# shelves_v05.net
KiCad netlist of a schematic drawn in EAGLE
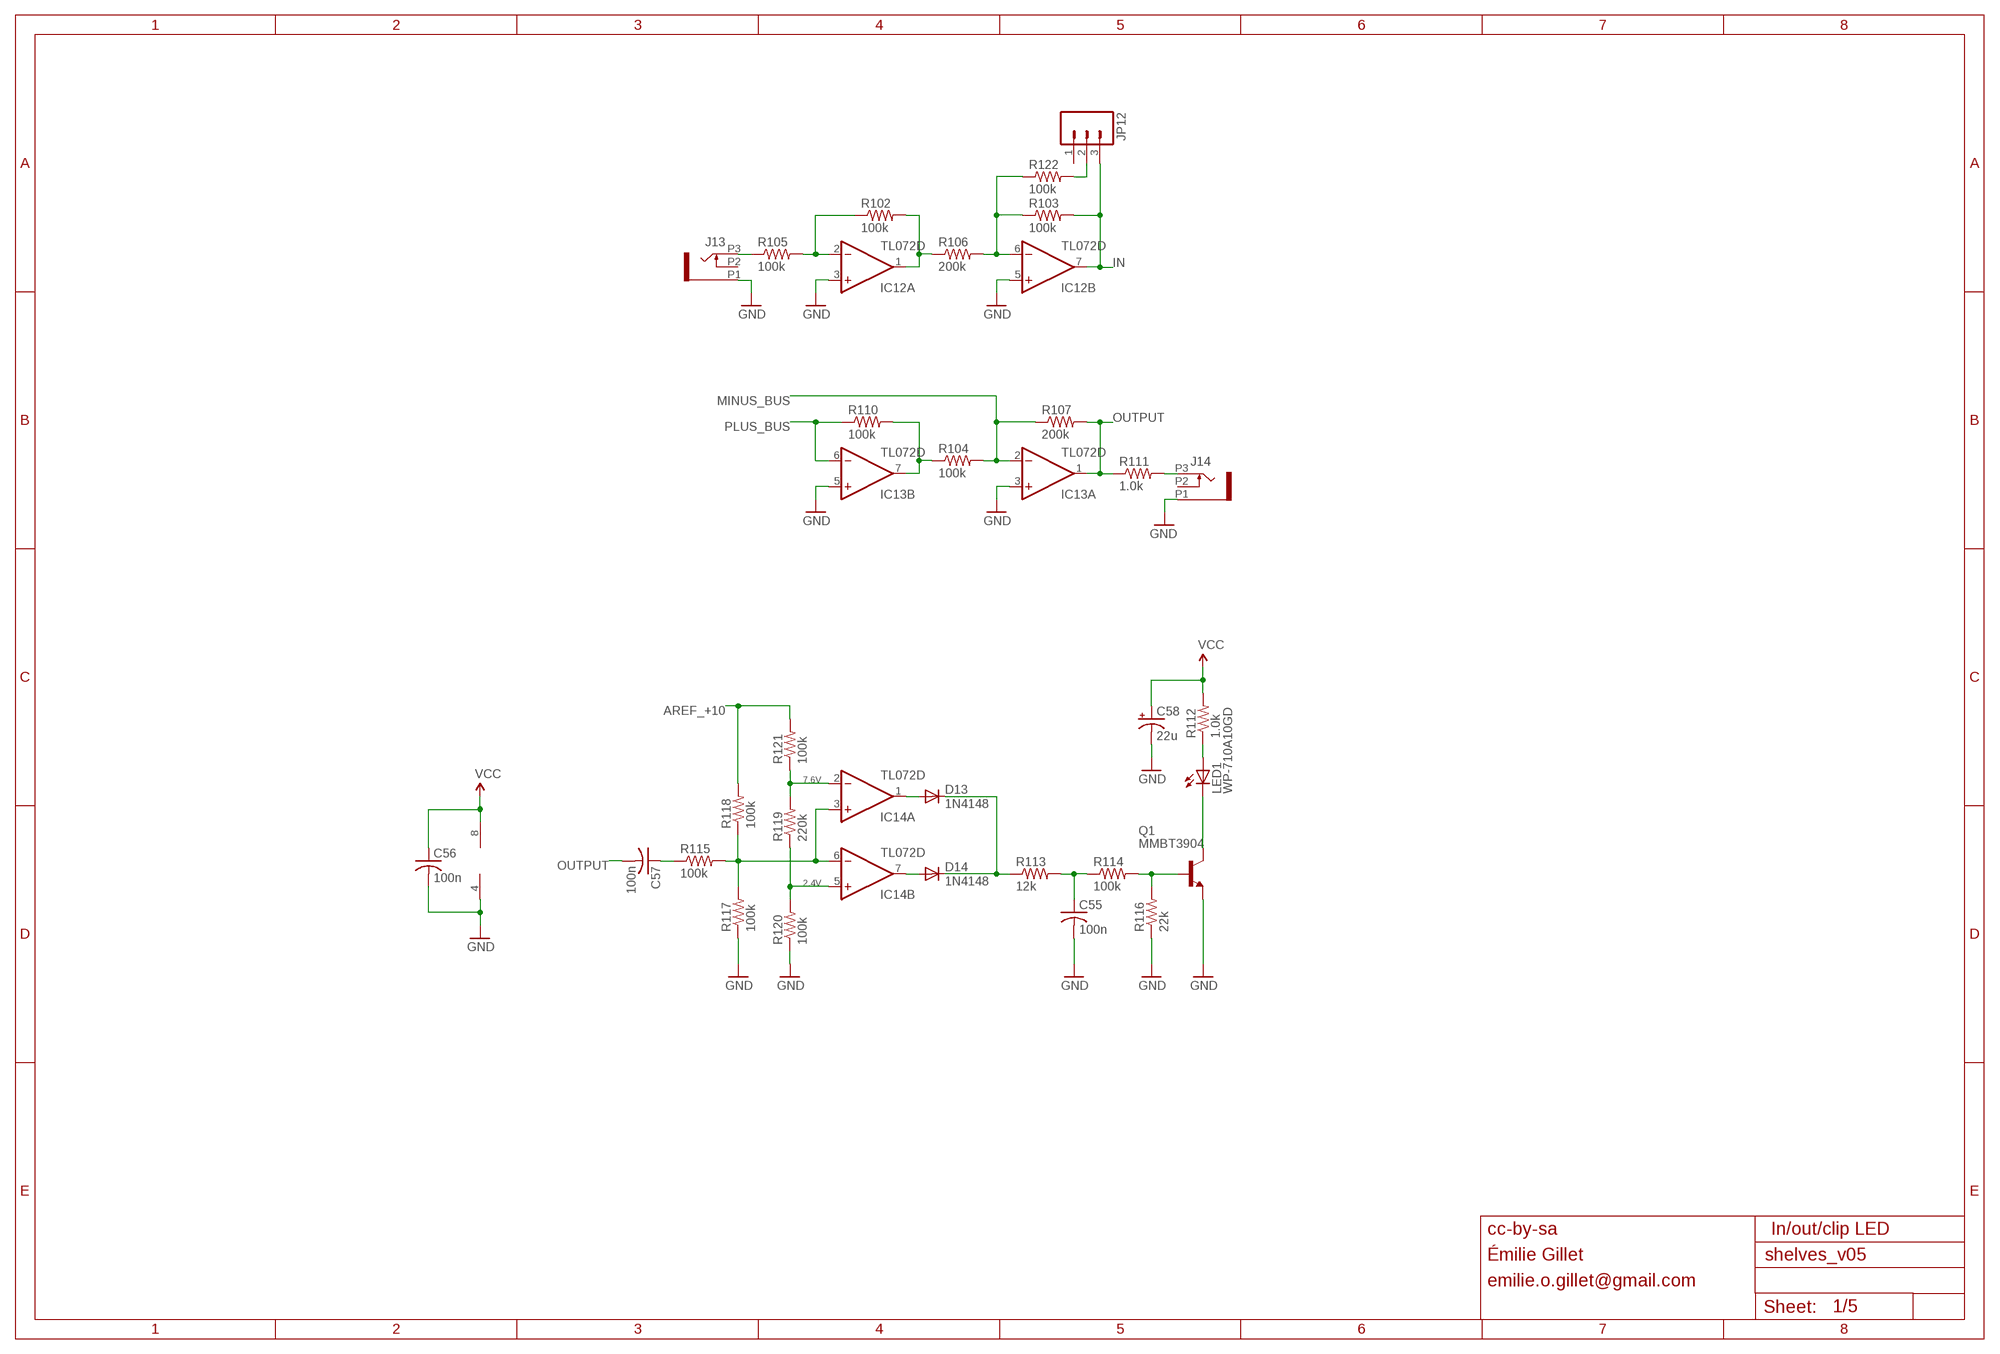
[diagram p0: schematic, sheet 1]
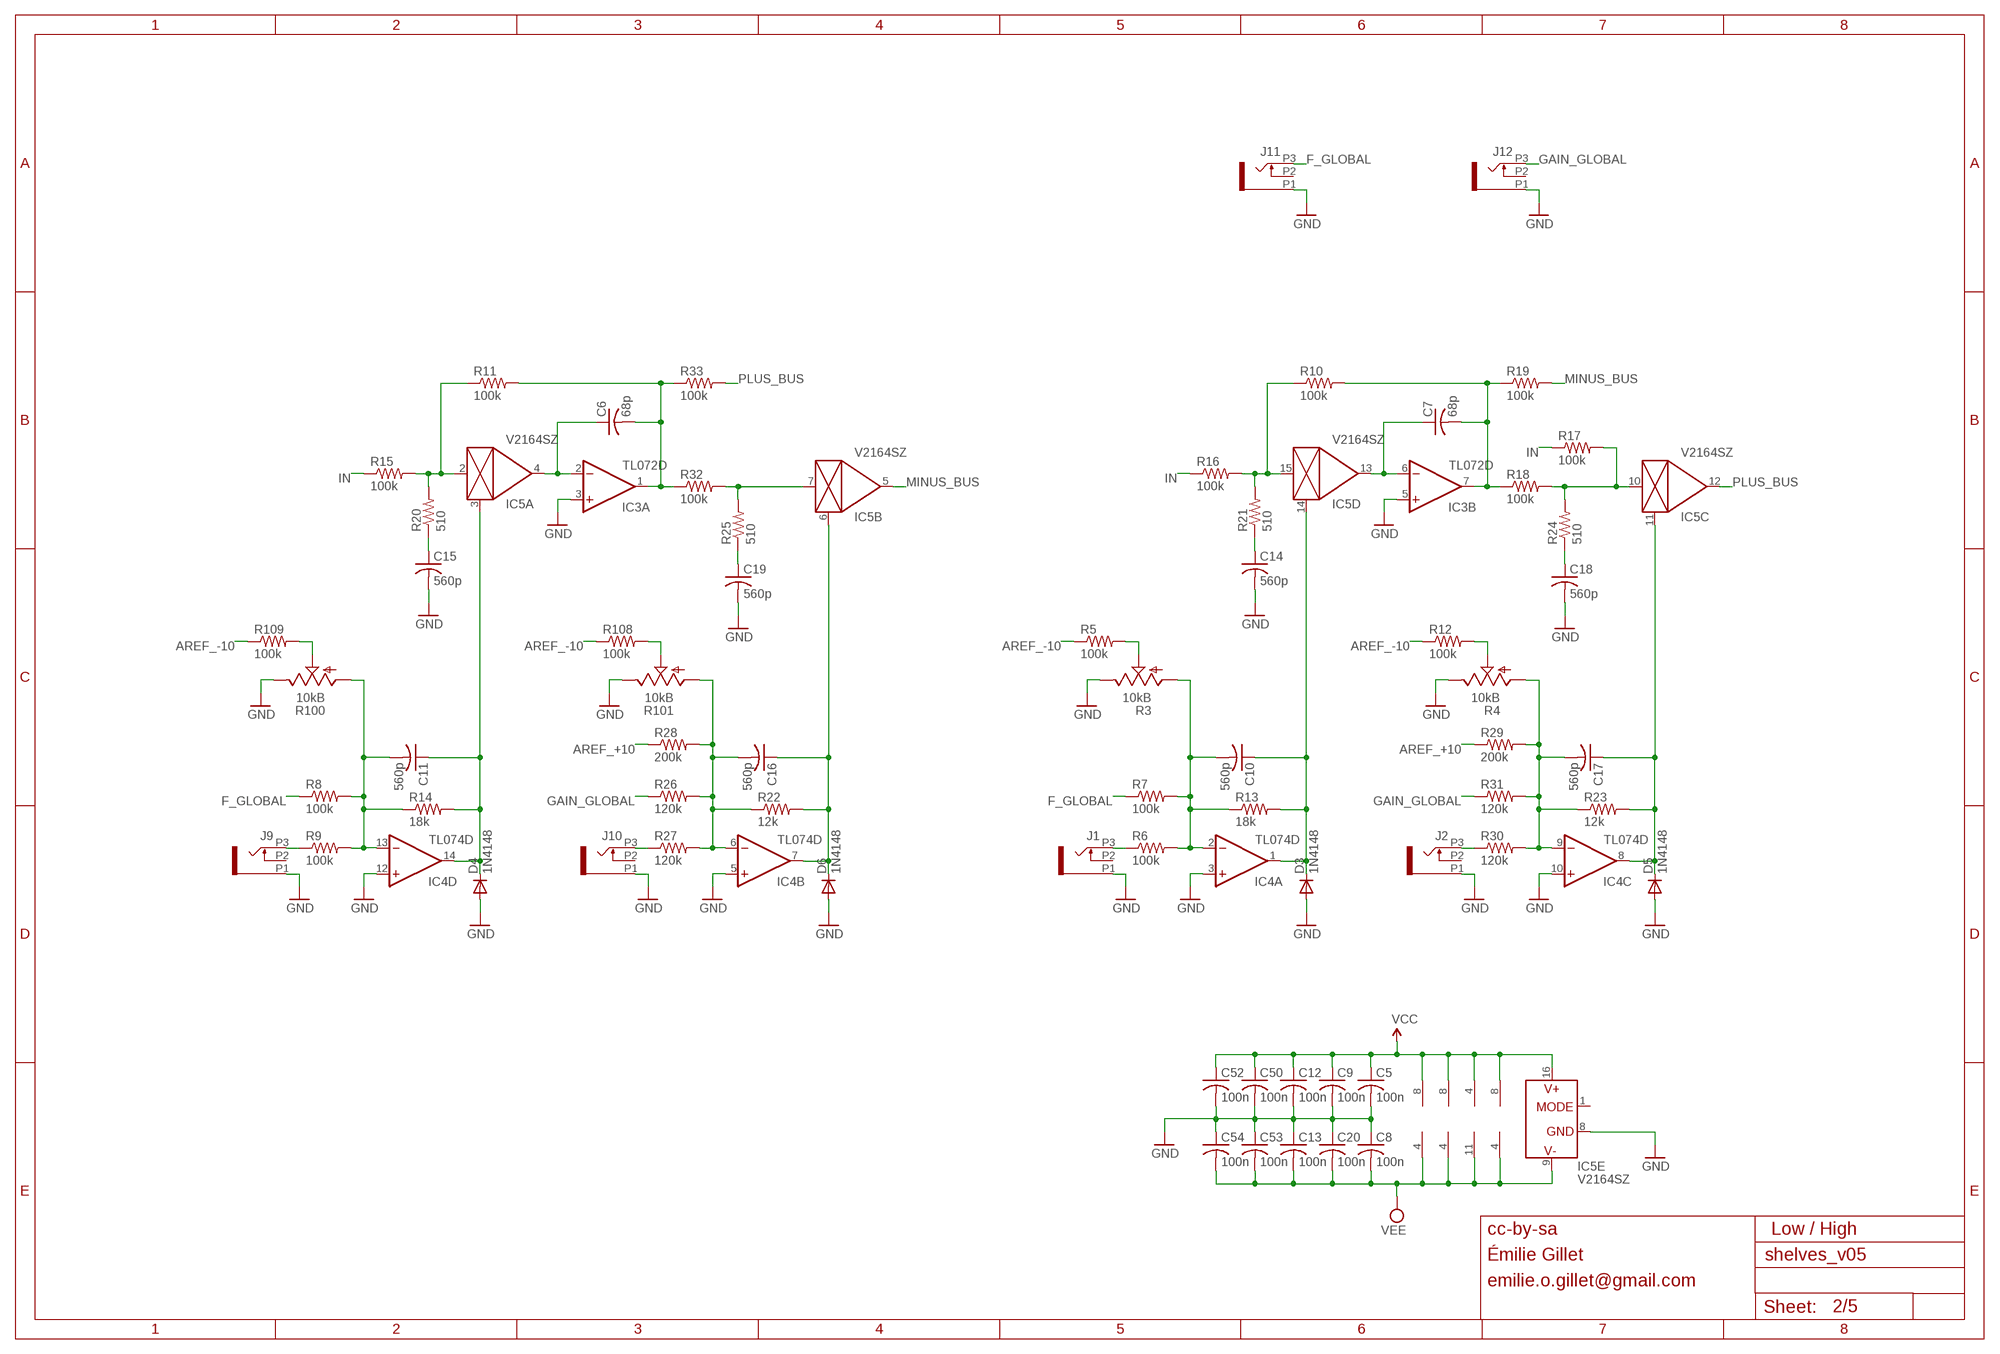
[diagram p1: schematic, sheet 2]
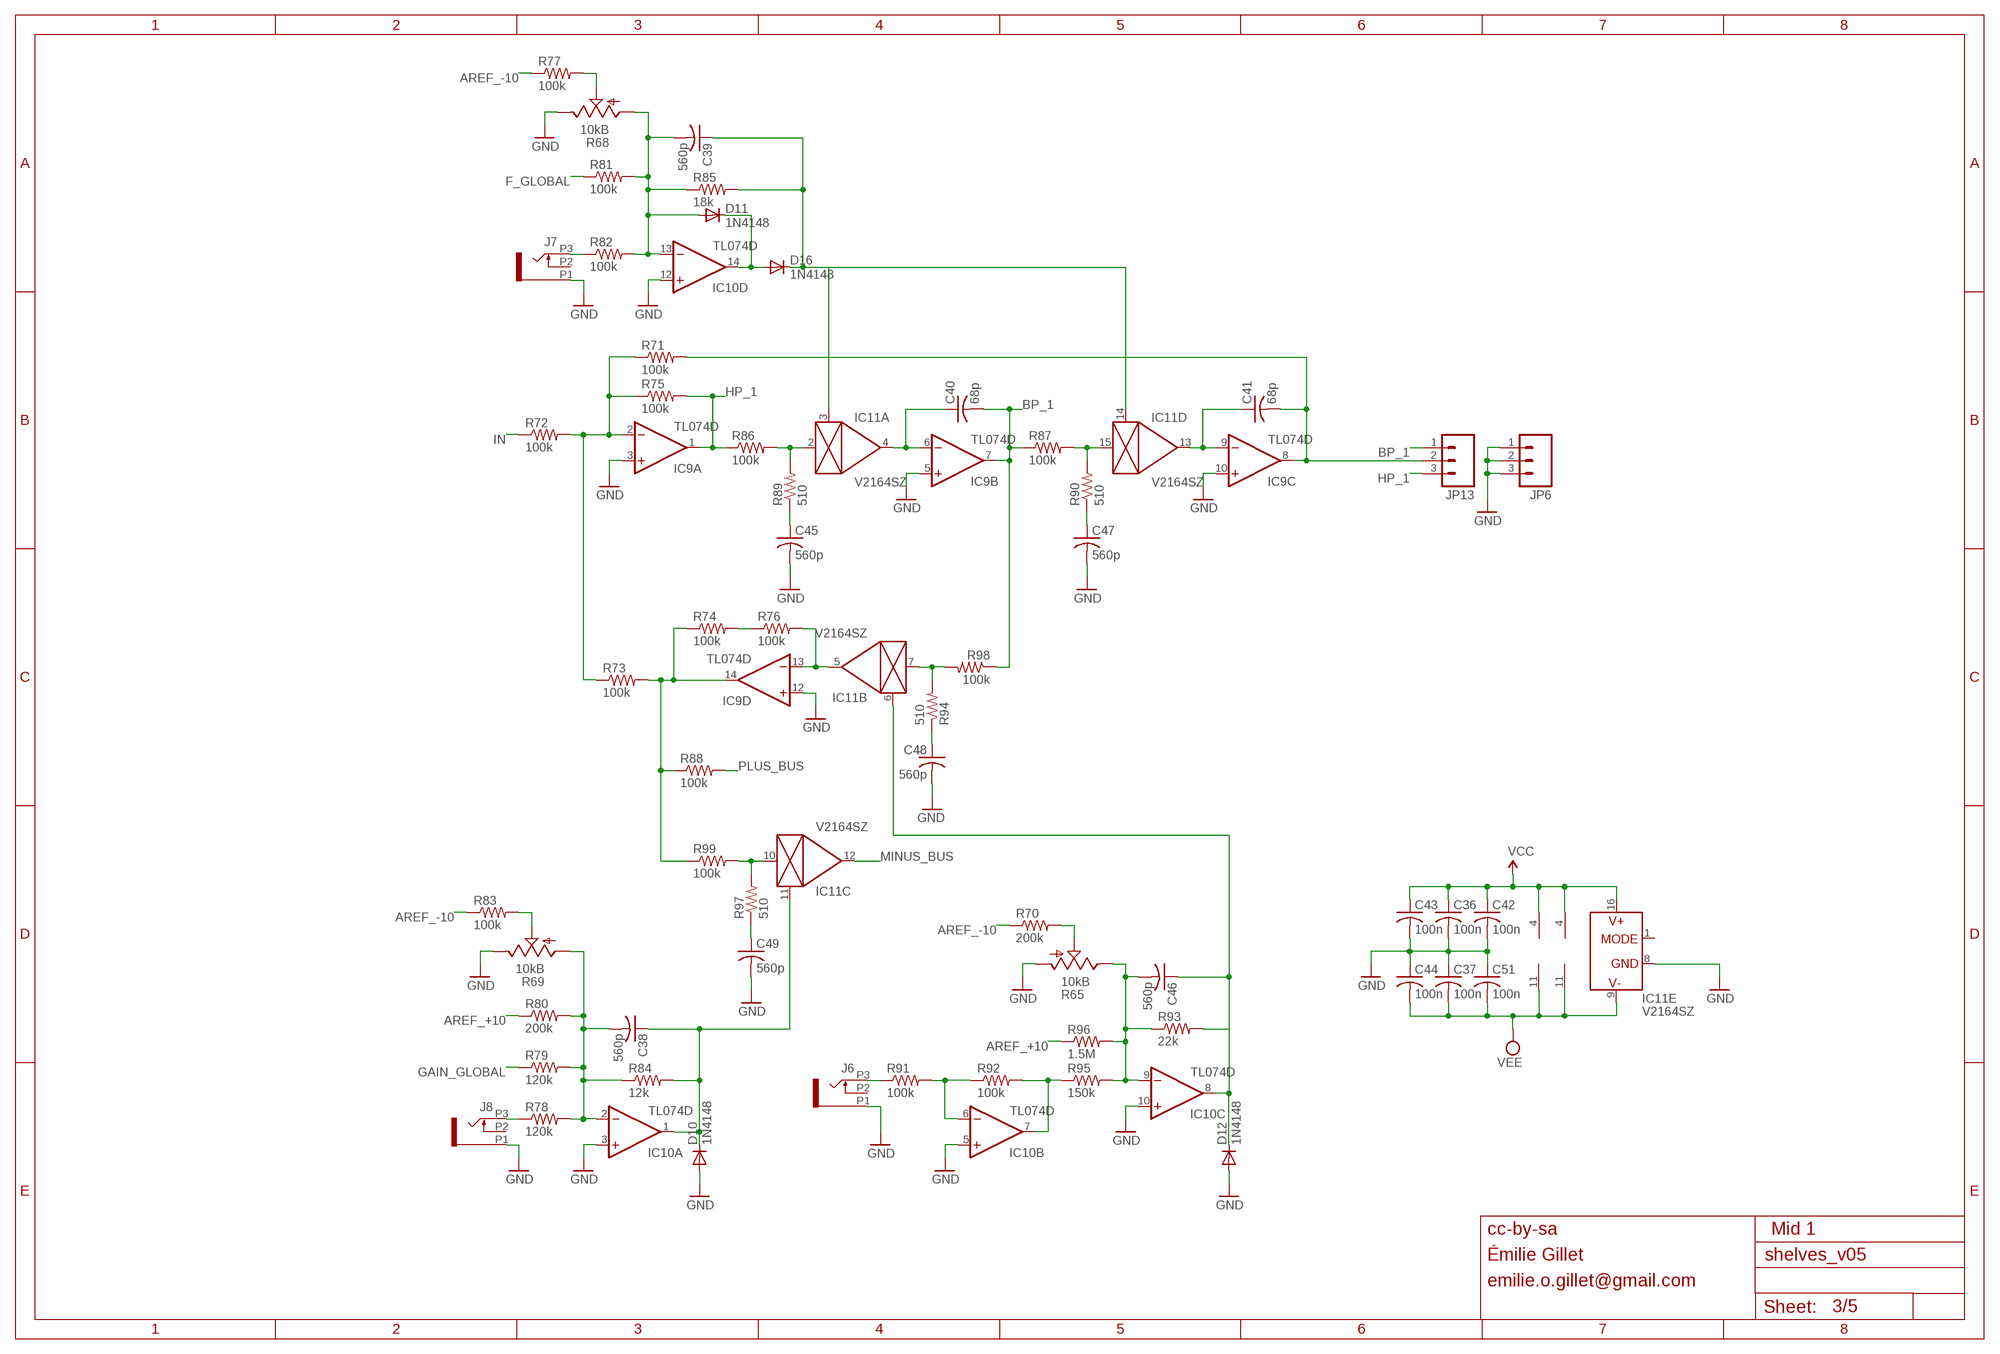
[diagram p2: schematic, sheet 3]
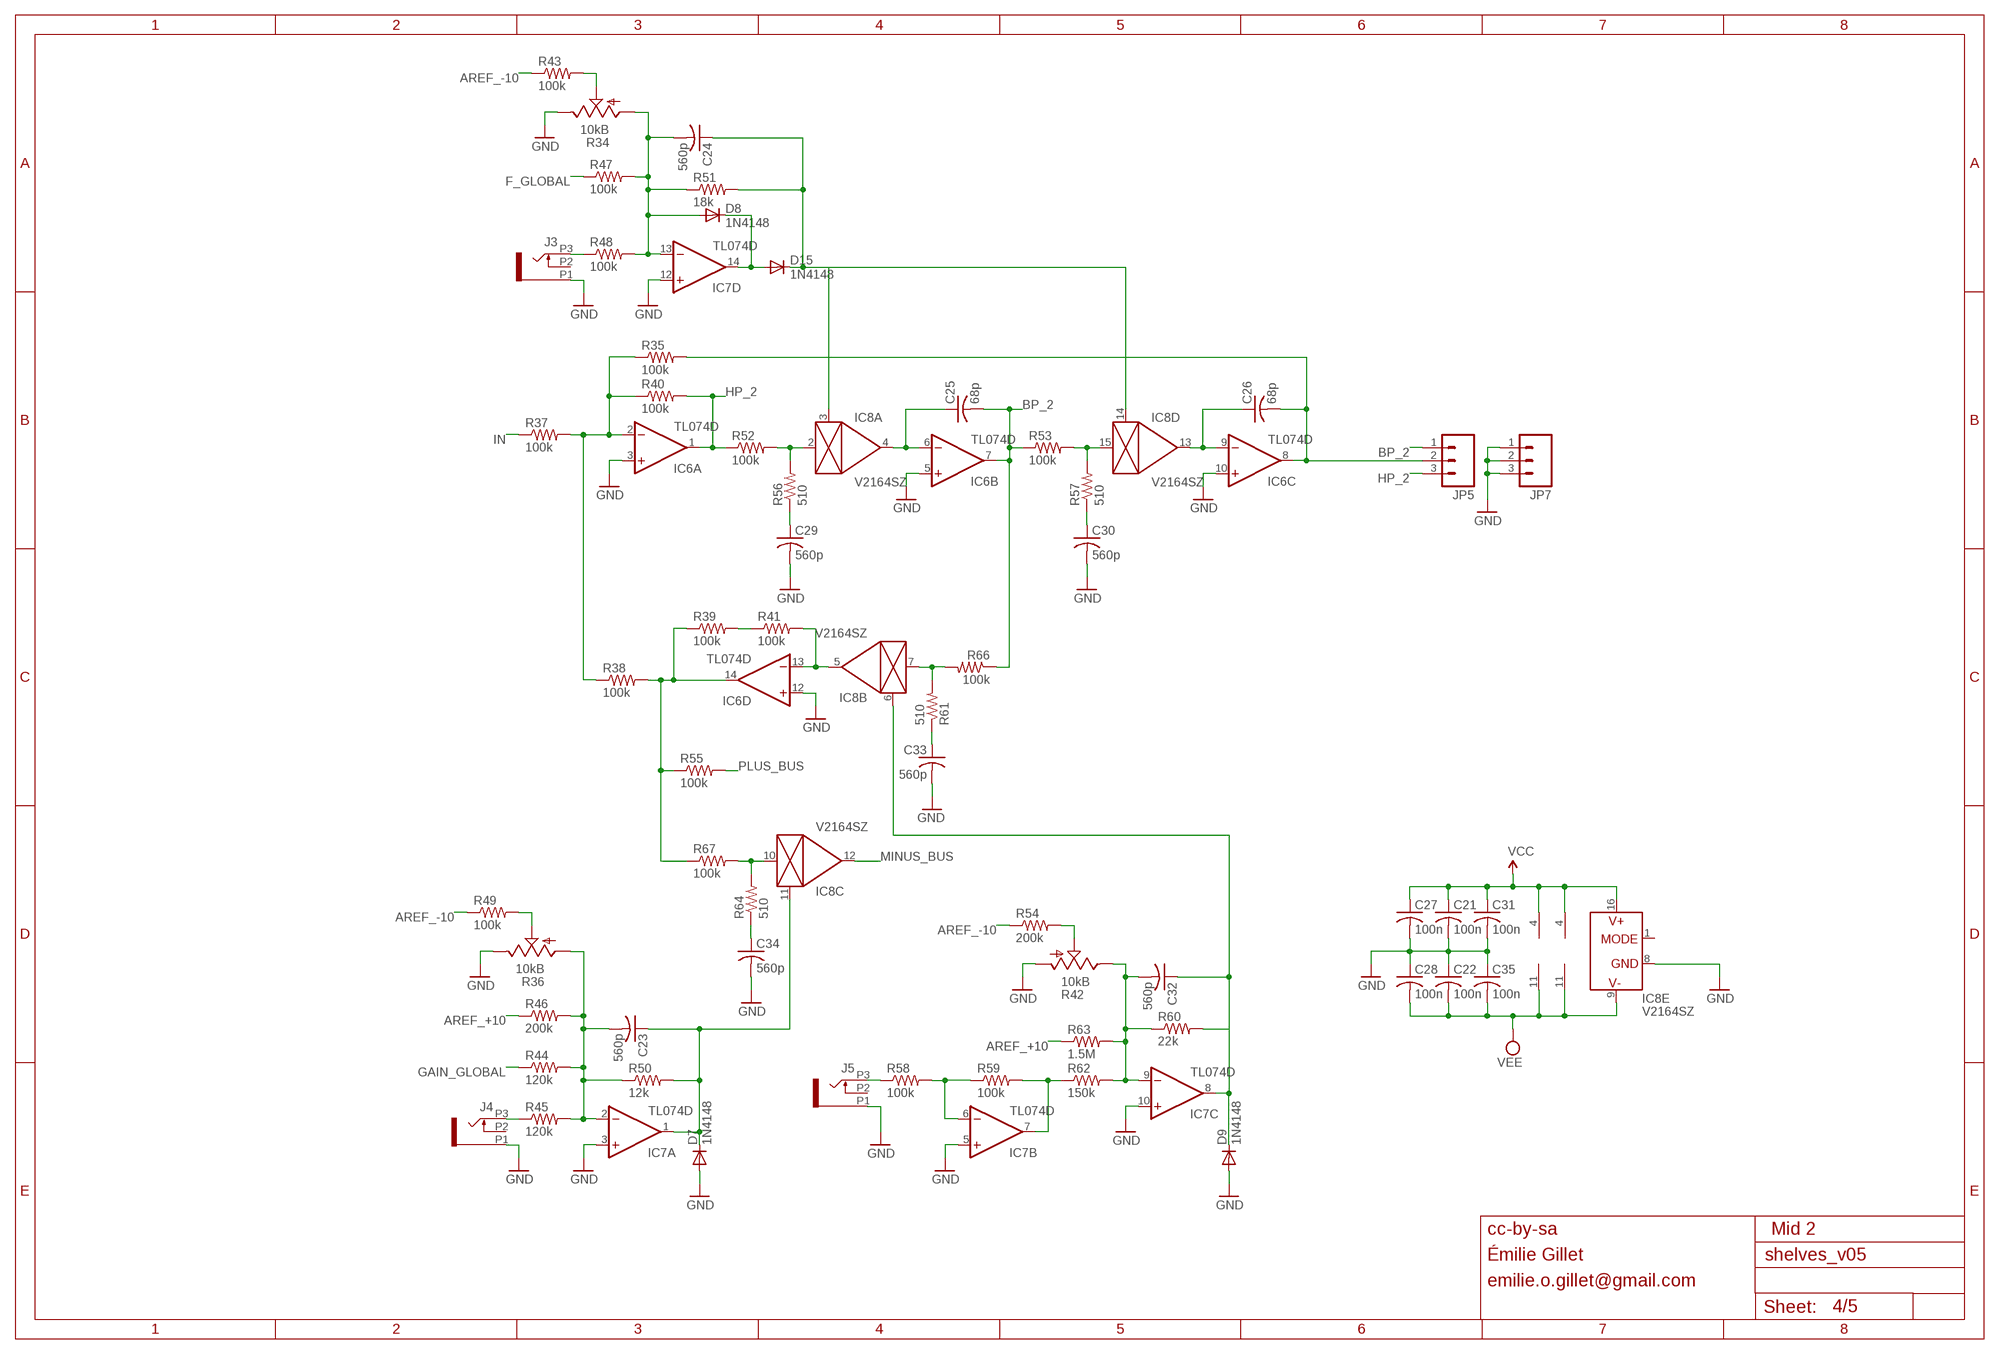
[diagram p3: schematic, sheet 4]
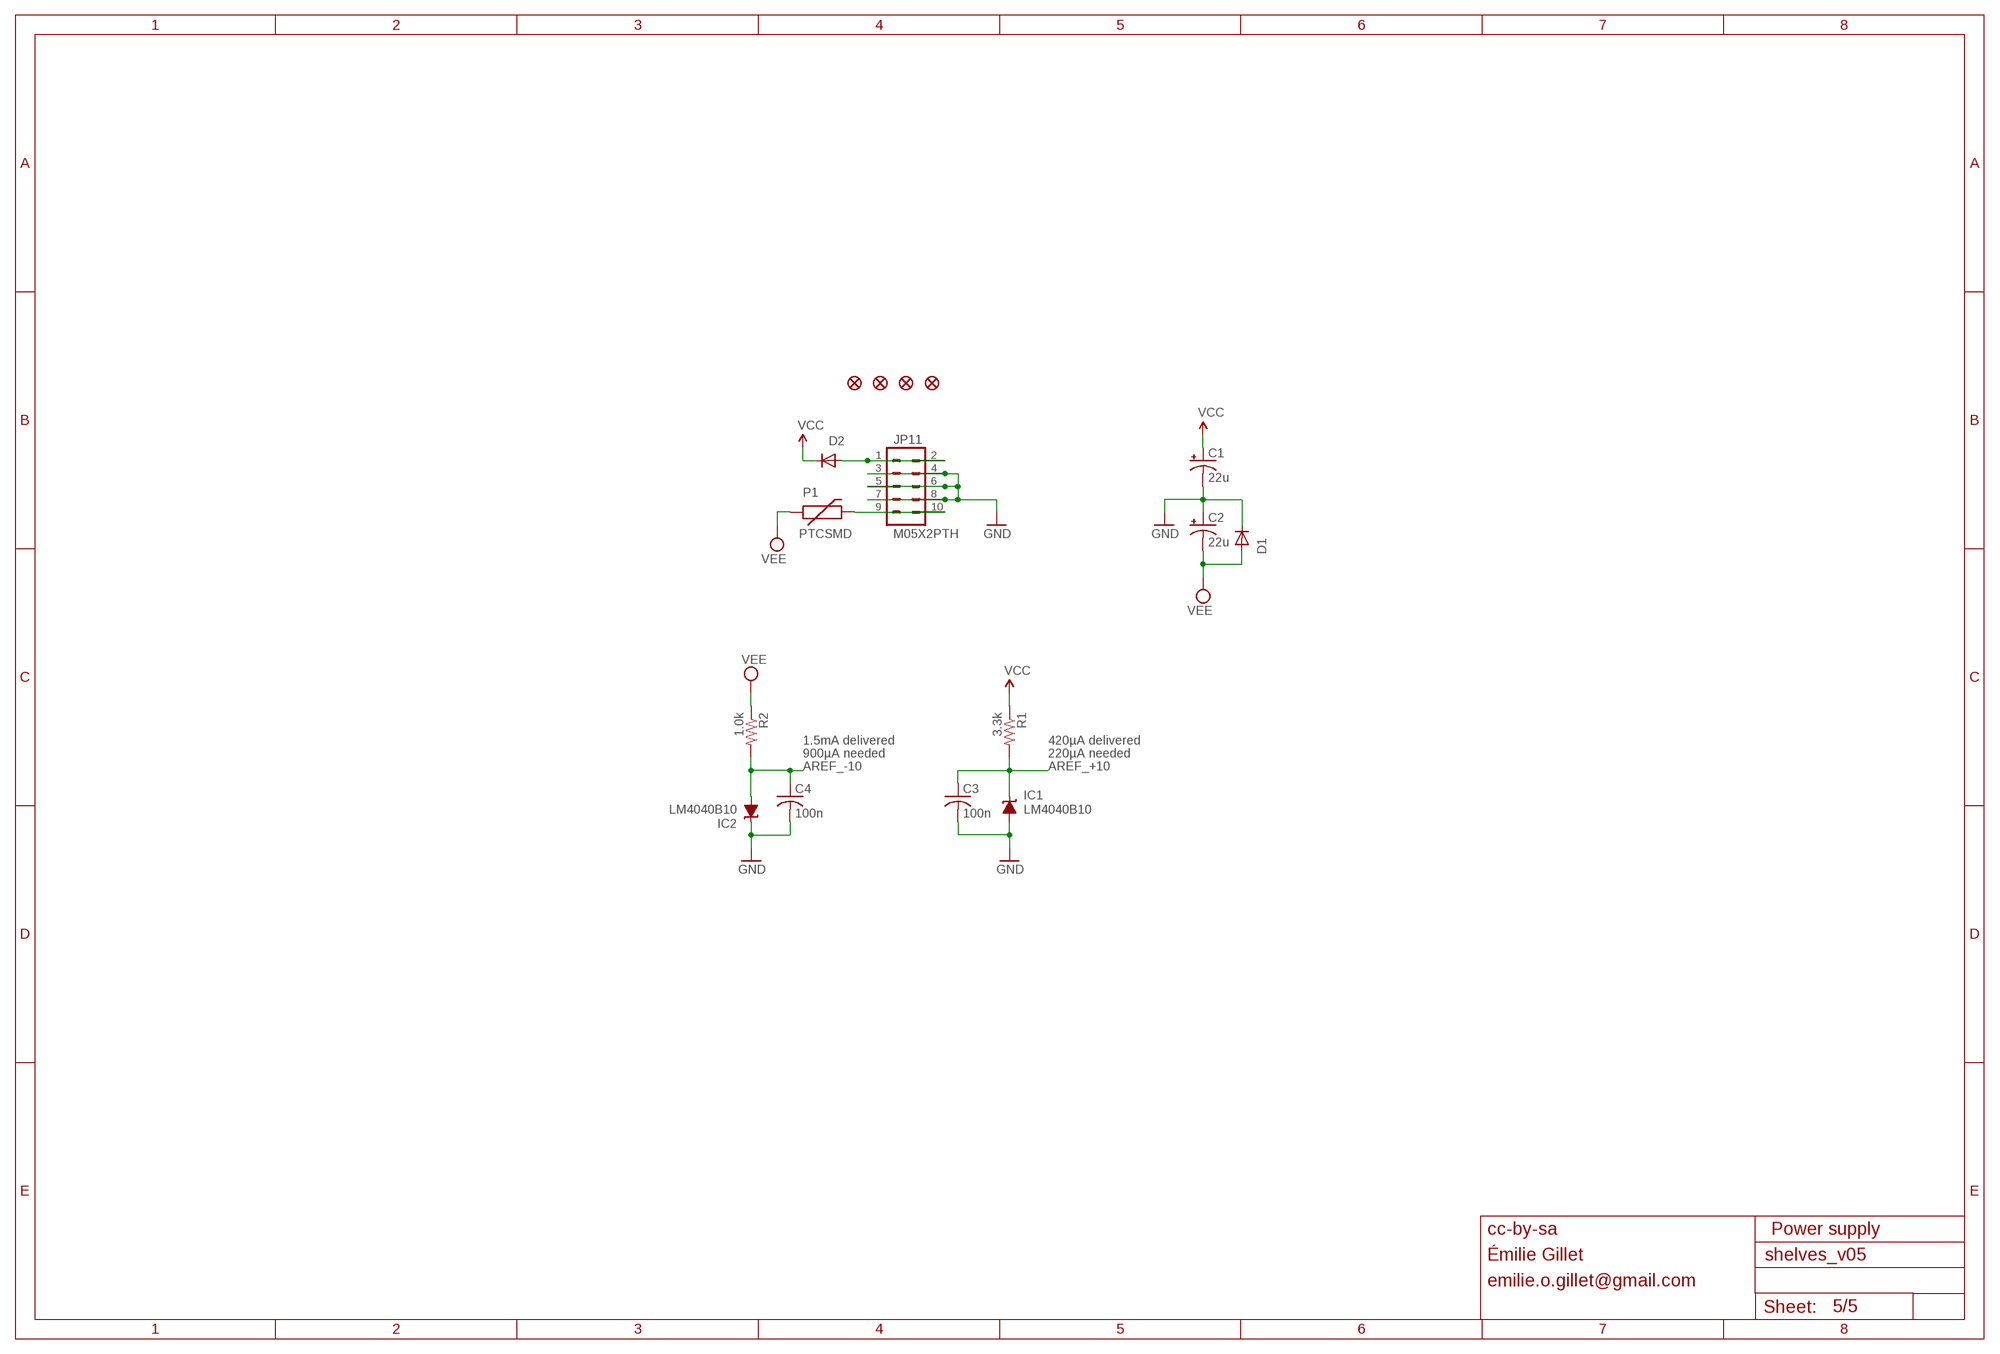
[diagram p4: schematic, sheet 5]

(export (version "E")
  (design (tool "Eeschema 10.0.6"))
  (components
    (comp (ref "C21")
      (value "100n")
      (footprint "eagle-import:C0603")
      (libsource (lib "eagle-import") (part "C-USC0603"))
    )
    (comp (ref "C22")
      (value "100n")
      (footprint "eagle-import:C0603")
      (libsource (lib "eagle-import") (part "C-USC0603"))
    )
    (comp (ref "C23")
      (value "560p")
      (footprint "eagle-import:C0603")
      (libsource (lib "eagle-import") (part "C-USC0603"))
    )
    (comp (ref "C24")
      (value "560p")
      (footprint "eagle-import:C0603")
      (libsource (lib "eagle-import") (part "C-USC0603"))
    )
    (comp (ref "C25")
      (value "68p")
      (footprint "eagle-import:C0603")
      (libsource (lib "eagle-import") (part "C-USC0603"))
    )
    (comp (ref "C26")
      (value "68p")
      (footprint "eagle-import:C0603")
      (libsource (lib "eagle-import") (part "C-USC0603"))
    )
    (comp (ref "C27")
      (value "100n")
      (footprint "eagle-import:C0603")
      (libsource (lib "eagle-import") (part "C-USC0603"))
    )
    (comp (ref "C28")
      (value "100n")
      (footprint "eagle-import:C0603")
      (libsource (lib "eagle-import") (part "C-USC0603"))
    )
    (comp (ref "C29")
      (value "560p")
      (footprint "eagle-import:C0603")
      (libsource (lib "eagle-import") (part "C-USC0603"))
    )
    (comp (ref "C30")
      (value "560p")
      (footprint "eagle-import:C0603")
      (libsource (lib "eagle-import") (part "C-USC0603"))
    )
    (comp (ref "C31")
      (value "100n")
      (footprint "eagle-import:C0603")
      (libsource (lib "eagle-import") (part "C-USC0603"))
    )
    (comp (ref "C32")
      (value "560p")
      (footprint "eagle-import:C0603")
      (libsource (lib "eagle-import") (part "C-USC0603"))
    )
    (comp (ref "C33")
      (value "560p")
      (footprint "eagle-import:C0603")
      (libsource (lib "eagle-import") (part "C-USC0603"))
    )
    (comp (ref "C34")
      (value "560p")
      (footprint "eagle-import:C0603")
      (libsource (lib "eagle-import") (part "C-USC0603"))
    )
    (comp (ref "C35")
      (value "100n")
      (footprint "eagle-import:C0603")
      (libsource (lib "eagle-import") (part "C-USC0603"))
    )
    (comp (ref "D7")
      (value "1N4148")
      (footprint "eagle-import:SOD323-W")
      (libsource (lib "eagle-import") (part "DIODE-SOD323-W"))
    )
    (comp (ref "D8")
      (value "1N4148")
      (footprint "eagle-import:SOD323-W")
      (libsource (lib "eagle-import") (part "DIODE-SOD323-W"))
    )
    (comp (ref "D9")
      (value "1N4148")
      (footprint "eagle-import:SOD323-W")
      (libsource (lib "eagle-import") (part "DIODE-SOD323-W"))
    )
    (comp (ref "D15")
      (value "1N4148")
      (footprint "eagle-import:SOD323-W")
      (libsource (lib "eagle-import") (part "DIODE-SOD323-W"))
    )
    (comp (ref "IC6")
      (value "TL074D")
      (footprint "eagle-import:SO14")
      (libsource (lib "eagle-import") (part "TL074D"))
    )
    (comp (ref "IC7")
      (value "TL074D")
      (footprint "eagle-import:SO14")
      (libsource (lib "eagle-import") (part "TL074D"))
    )
    (comp (ref "IC8")
      (value "V2164SZ")
      (footprint "eagle-import:SOIC16N")
      (libsource (lib "eagle-import") (part "SSM2164S"))
    )
    (comp (ref "J3")
      (value "PJ301_THONKICONN6")
      (footprint "eagle-import:WQP_PJ_301M6")
      (libsource (lib "eagle-import") (part "PJ301_THONKICONN6"))
    )
    (comp (ref "J4")
      (value "PJ301_THONKICONN6")
      (footprint "eagle-import:WQP_PJ_301M6")
      (libsource (lib "eagle-import") (part "PJ301_THONKICONN6"))
    )
    (comp (ref "J5")
      (value "PJ301_THONKICONN6")
      (footprint "eagle-import:WQP_PJ_301M6")
      (libsource (lib "eagle-import") (part "PJ301_THONKICONN6"))
    )
    (comp (ref "JP5")
      (value "M03PTH")
      (footprint "eagle-import:1X03")
      (libsource (lib "eagle-import") (part "M03PTH"))
    )
    (comp (ref "JP7")
      (value "M03PTH")
      (footprint "eagle-import:1X03")
      (libsource (lib "eagle-import") (part "M03PTH"))
    )
    (comp (ref "R34")
      (value "10kB")
      (footprint "eagle-import:ALPS_POT_VERTICAL_PS")
      (libsource (lib "eagle-import") (part "POT_USVERTICAL_PS"))
    )
    (comp (ref "R35")
      (value "100k")
      (footprint "eagle-import:R0603")
      (libsource (lib "eagle-import") (part "R-US_R0603"))
    )
    (comp (ref "R36")
      (value "10kB")
      (footprint "eagle-import:ALPS_POT_VERTICAL_PS")
      (libsource (lib "eagle-import") (part "POT_USVERTICAL_PS"))
    )
    (comp (ref "R37")
      (value "100k")
      (footprint "eagle-import:R0603")
      (libsource (lib "eagle-import") (part "R-US_R0603"))
    )
    (comp (ref "R38")
      (value "100k")
      (footprint "eagle-import:R0603")
      (libsource (lib "eagle-import") (part "R-US_R0603"))
    )
    (comp (ref "R39")
      (value "100k")
      (footprint "eagle-import:R0603")
      (libsource (lib "eagle-import") (part "R-US_R0603"))
    )
    (comp (ref "R40")
      (value "100k")
      (footprint "eagle-import:R0603")
      (libsource (lib "eagle-import") (part "R-US_R0603"))
    )
    (comp (ref "R41")
      (value "100k")
      (footprint "eagle-import:R0603")
      (libsource (lib "eagle-import") (part "R-US_R0603"))
    )
    (comp (ref "R42")
      (value "10kB")
      (footprint "eagle-import:ALPS_POT_VERTICAL")
      (libsource (lib "eagle-import") (part "POT_USVERTICAL"))
    )
    (comp (ref "R43")
      (value "100k")
      (footprint "eagle-import:R0603")
      (libsource (lib "eagle-import") (part "R-US_R0603"))
    )
    (comp (ref "R44")
      (value "120k")
      (footprint "eagle-import:R0603")
      (libsource (lib "eagle-import") (part "R-US_R0603"))
    )
    (comp (ref "R45")
      (value "120k")
      (footprint "eagle-import:R0603")
      (libsource (lib "eagle-import") (part "R-US_R0603"))
    )
    (comp (ref "R46")
      (value "200k")
      (footprint "eagle-import:R0603")
      (libsource (lib "eagle-import") (part "R-US_R0603"))
    )
    (comp (ref "R47")
      (value "100k")
      (footprint "eagle-import:R0603")
      (libsource (lib "eagle-import") (part "R-US_R0603"))
    )
    (comp (ref "R48")
      (value "100k")
      (footprint "eagle-import:R0603")
      (libsource (lib "eagle-import") (part "R-US_R0603"))
    )
    (comp (ref "R49")
      (value "100k")
      (footprint "eagle-import:R0603")
      (libsource (lib "eagle-import") (part "R-US_R0603"))
    )
    (comp (ref "R50")
      (value "12k")
      (footprint "eagle-import:R0603")
      (libsource (lib "eagle-import") (part "R-US_R0603"))
    )
    (comp (ref "R51")
      (value "18k")
      (footprint "eagle-import:R0603")
      (libsource (lib "eagle-import") (part "R-US_R0603"))
    )
    (comp (ref "R52")
      (value "100k")
      (footprint "eagle-import:R0603")
      (libsource (lib "eagle-import") (part "R-US_R0603"))
    )
    (comp (ref "R53")
      (value "100k")
      (footprint "eagle-import:R0603")
      (libsource (lib "eagle-import") (part "R-US_R0603"))
    )
    (comp (ref "R54")
      (value "200k")
      (footprint "eagle-import:R0603")
      (libsource (lib "eagle-import") (part "R-US_R0603"))
    )
    (comp (ref "R55")
      (value "100k")
      (footprint "eagle-import:R0603")
      (libsource (lib "eagle-import") (part "R-US_R0603"))
    )
    (comp (ref "R56")
      (value "510")
      (footprint "eagle-import:R0603")
      (libsource (lib "eagle-import") (part "R-US_R0603"))
    )
    (comp (ref "R57")
      (value "510")
      (footprint "eagle-import:R0603")
      (libsource (lib "eagle-import") (part "R-US_R0603"))
    )
    (comp (ref "R58")
      (value "100k")
      (footprint "eagle-import:R0603")
      (libsource (lib "eagle-import") (part "R-US_R0603"))
    )
    (comp (ref "R59")
      (value "100k")
      (footprint "eagle-import:R0603")
      (libsource (lib "eagle-import") (part "R-US_R0603"))
    )
    (comp (ref "R60")
      (value "22k")
      (footprint "eagle-import:R0603")
      (libsource (lib "eagle-import") (part "R-US_R0603"))
    )
    (comp (ref "R61")
      (value "510")
      (footprint "eagle-import:R0603")
      (libsource (lib "eagle-import") (part "R-US_R0603"))
    )
    (comp (ref "R62")
      (value "150k")
      (footprint "eagle-import:R0603")
      (libsource (lib "eagle-import") (part "R-US_R0603"))
    )
    (comp (ref "R63")
      (value "1.5M")
      (footprint "eagle-import:R0603")
      (libsource (lib "eagle-import") (part "R-US_R0603"))
    )
    (comp (ref "R64")
      (value "510")
      (footprint "eagle-import:R0603")
      (libsource (lib "eagle-import") (part "R-US_R0603"))
    )
    (comp (ref "R66")
      (value "100k")
      (footprint "eagle-import:R0603")
      (libsource (lib "eagle-import") (part "R-US_R0603"))
    )
    (comp (ref "R67")
      (value "100k")
      (footprint "eagle-import:R0603")
      (libsource (lib "eagle-import") (part "R-US_R0603"))
    )
    (comp (ref "C55")
      (value "100n")
      (footprint "eagle-import:C0603")
      (libsource (lib "eagle-import") (part "C-USC0603"))
    )
    (comp (ref "C56")
      (value "100n")
      (footprint "eagle-import:C0603")
      (libsource (lib "eagle-import") (part "C-USC0603"))
    )
    (comp (ref "C57")
      (value "100n")
      (footprint "eagle-import:C0603")
      (libsource (lib "eagle-import") (part "C-USC0603"))
    )
    (comp (ref "C58")
      (value "22u")
      (footprint "eagle-import:PANASONIC_C")
      (libsource (lib "eagle-import") (part "CPOL-USC"))
    )
    (comp (ref "D13")
      (value "1N4148")
      (footprint "eagle-import:SOD323-W")
      (libsource (lib "eagle-import") (part "DIODE-SOD323-W"))
    )
    (comp (ref "D14")
      (value "1N4148")
      (footprint "eagle-import:SOD323-W")
      (libsource (lib "eagle-import") (part "DIODE-SOD323-W"))
    )
    (comp (ref "IC12")
      (value "TL072D")
      (footprint "eagle-import:SO08")
      (libsource (lib "eagle-import") (part "TL072D"))
    )
    (comp (ref "IC13")
      (value "TL072D")
      (footprint "eagle-import:SO08")
      (libsource (lib "eagle-import") (part "TL072D"))
    )
    (comp (ref "IC14")
      (value "TL072D")
      (footprint "eagle-import:SO08")
      (libsource (lib "eagle-import") (part "TL072D"))
    )
    (comp (ref "J13")
      (value "PJ301_THONKICONN6")
      (footprint "eagle-import:WQP_PJ_301M6")
      (libsource (lib "eagle-import") (part "PJ301_THONKICONN6"))
    )
    (comp (ref "J14")
      (value "PJ301_THONKICONN6")
      (footprint "eagle-import:WQP_PJ_301M6")
      (libsource (lib "eagle-import") (part "PJ301_THONKICONN6"))
    )
    (comp (ref "JP12")
      (value "M03PTH")
      (footprint "eagle-import:1X03")
      (libsource (lib "eagle-import") (part "M03PTH"))
    )
    (comp (ref "LED1")
      (value "WP-710A10GD")
      (footprint "eagle-import:LED3MM")
      (libsource (lib "eagle-import") (part "LED3MM"))
    )
    (comp (ref "Q1")
      (value "MMBT3904")
      (footprint "eagle-import:SOT23-BEC")
      (libsource (lib "eagle-import") (part "-NPN-SOT23-BECMMBT3904LT1"))
    )
    (comp (ref "R102")
      (value "100k")
      (footprint "eagle-import:R0603")
      (libsource (lib "eagle-import") (part "R-US_R0603"))
    )
    (comp (ref "R103")
      (value "100k")
      (footprint "eagle-import:R0603")
      (libsource (lib "eagle-import") (part "R-US_R0603"))
    )
    (comp (ref "R104")
      (value "100k")
      (footprint "eagle-import:R0603")
      (libsource (lib "eagle-import") (part "R-US_R0603"))
    )
    (comp (ref "R105")
      (value "100k")
      (footprint "eagle-import:R0603")
      (libsource (lib "eagle-import") (part "R-US_R0603"))
    )
    (comp (ref "R106")
      (value "200k")
      (footprint "eagle-import:R0603")
      (libsource (lib "eagle-import") (part "R-US_R0603"))
    )
    (comp (ref "R107")
      (value "200k")
      (footprint "eagle-import:R0603")
      (libsource (lib "eagle-import") (part "R-US_R0603"))
    )
    (comp (ref "R110")
      (value "100k")
      (footprint "eagle-import:R0603")
      (libsource (lib "eagle-import") (part "R-US_R0603"))
    )
    (comp (ref "R111")
      (value "1.0k")
      (footprint "eagle-import:R0603")
      (libsource (lib "eagle-import") (part "R-US_R0603"))
    )
    (comp (ref "R112")
      (value "1.0k")
      (footprint "eagle-import:R0603")
      (libsource (lib "eagle-import") (part "R-US_R0603"))
    )
    (comp (ref "R113")
      (value "12k")
      (footprint "eagle-import:R0603")
      (libsource (lib "eagle-import") (part "R-US_R0603"))
    )
    (comp (ref "R114")
      (value "100k")
      (footprint "eagle-import:R0603")
      (libsource (lib "eagle-import") (part "R-US_R0603"))
    )
    (comp (ref "R115")
      (value "100k")
      (footprint "eagle-import:R0603")
      (libsource (lib "eagle-import") (part "R-US_R0603"))
    )
    (comp (ref "R116")
      (value "22k")
      (footprint "eagle-import:R0603")
      (libsource (lib "eagle-import") (part "R-US_R0603"))
    )
    (comp (ref "R117")
      (value "100k")
      (footprint "eagle-import:R0603")
      (libsource (lib "eagle-import") (part "R-US_R0603"))
    )
    (comp (ref "R118")
      (value "100k")
      (footprint "eagle-import:R0603")
      (libsource (lib "eagle-import") (part "R-US_R0603"))
    )
    (comp (ref "R119")
      (value "220k")
      (footprint "eagle-import:R0603")
      (libsource (lib "eagle-import") (part "R-US_R0603"))
    )
    (comp (ref "R120")
      (value "100k")
      (footprint "eagle-import:R0603")
      (libsource (lib "eagle-import") (part "R-US_R0603"))
    )
    (comp (ref "R121")
      (value "100k")
      (footprint "eagle-import:R0603")
      (libsource (lib "eagle-import") (part "R-US_R0603"))
    )
    (comp (ref "R122")
      (value "100k")
      (footprint "eagle-import:R0603")
      (libsource (lib "eagle-import") (part "R-US_R0603"))
    )
    (comp (ref "C1")
      (value "22u")
      (footprint "eagle-import:PANASONIC_C")
      (libsource (lib "eagle-import") (part "CPOL-USC"))
    )
    (comp (ref "C2")
      (value "22u")
      (footprint "eagle-import:PANASONIC_C")
      (libsource (lib "eagle-import") (part "CPOL-USC"))
    )
    (comp (ref "C3")
      (value "100n")
      (footprint "eagle-import:C0603")
      (libsource (lib "eagle-import") (part "C-USC0603"))
    )
    (comp (ref "C4")
      (value "100n")
      (footprint "eagle-import:C0603")
      (libsource (lib "eagle-import") (part "C-USC0603"))
    )
    (comp (ref "D1")
      (value "1N5819HW")
      (footprint "eagle-import:SOD123")
      (libsource (lib "eagle-import") (part "DIODE-SOD123"))
    )
    (comp (ref "D2")
      (value "1N5819HW")
      (footprint "eagle-import:SOD123")
      (libsource (lib "eagle-import") (part "DIODE-SOD123"))
    )
    (comp (ref "IC1")
      (value "LM4040B10")
      (footprint "eagle-import:DBZ_R-PDSO-G3")
      (libsource (lib "eagle-import") (part "LM4041DBZB12"))
    )
    (comp (ref "IC2")
      (value "LM4040B10")
      (footprint "eagle-import:DBZ_R-PDSO-G3")
      (libsource (lib "eagle-import") (part "LM4041DBZB12"))
    )
    (comp (ref "JP1")
      (value "FIDUCIAL1X2")
      (footprint "eagle-import:FIDUCIAL-1X2")
      (libsource (lib "eagle-import") (part "FIDUCIAL1X2"))
    )
    (comp (ref "JP2")
      (value "FIDUCIAL1X2")
      (footprint "eagle-import:FIDUCIAL-1X2")
      (libsource (lib "eagle-import") (part "FIDUCIAL1X2"))
    )
    (comp (ref "JP3")
      (value "FIDUCIAL1X2")
      (footprint "eagle-import:FIDUCIAL-1X2")
      (libsource (lib "eagle-import") (part "FIDUCIAL1X2"))
    )
    (comp (ref "JP4")
      (value "FIDUCIAL1X2")
      (footprint "eagle-import:FIDUCIAL-1X2")
      (libsource (lib "eagle-import") (part "FIDUCIAL1X2"))
    )
    (comp (ref "JP11")
      (value "M05X2PTH")
      (footprint "eagle-import:AVR_ICSP")
      (libsource (lib "eagle-import") (part "M05X2PTH"))
    )
    (comp (ref "P1")
      (value "PTCSMD")
      (footprint "eagle-import:PTC-1206")
      (libsource (lib "eagle-import") (part "PTCSMD"))
    )
    (comp (ref "R1")
      (value "3.3k")
      (footprint "eagle-import:R0603")
      (libsource (lib "eagle-import") (part "R-US_R0603"))
    )
    (comp (ref "R2")
      (value "1.0k")
      (footprint "eagle-import:R0603")
      (libsource (lib "eagle-import") (part "R-US_R0603"))
    )
    (comp (ref "C5")
      (value "100n")
      (footprint "eagle-import:C0603")
      (libsource (lib "eagle-import") (part "C-USC0603"))
    )
    (comp (ref "C6")
      (value "68p")
      (footprint "eagle-import:C0603")
      (libsource (lib "eagle-import") (part "C-USC0603"))
    )
    (comp (ref "C7")
      (value "68p")
      (footprint "eagle-import:C0603")
      (libsource (lib "eagle-import") (part "C-USC0603"))
    )
    (comp (ref "C8")
      (value "100n")
      (footprint "eagle-import:C0603")
      (libsource (lib "eagle-import") (part "C-USC0603"))
    )
    (comp (ref "C9")
      (value "100n")
      (footprint "eagle-import:C0603")
      (libsource (lib "eagle-import") (part "C-USC0603"))
    )
    (comp (ref "C10")
      (value "560p")
      (footprint "eagle-import:C0603")
      (libsource (lib "eagle-import") (part "C-USC0603"))
    )
    (comp (ref "C11")
      (value "560p")
      (footprint "eagle-import:C0603")
      (libsource (lib "eagle-import") (part "C-USC0603"))
    )
    (comp (ref "C12")
      (value "100n")
      (footprint "eagle-import:C0603")
      (libsource (lib "eagle-import") (part "C-USC0603"))
    )
    (comp (ref "C13")
      (value "100n")
      (footprint "eagle-import:C0603")
      (libsource (lib "eagle-import") (part "C-USC0603"))
    )
    (comp (ref "C14")
      (value "560p")
      (footprint "eagle-import:C0603")
      (libsource (lib "eagle-import") (part "C-USC0603"))
    )
    (comp (ref "C15")
      (value "560p")
      (footprint "eagle-import:C0603")
      (libsource (lib "eagle-import") (part "C-USC0603"))
    )
    (comp (ref "C16")
      (value "560p")
      (footprint "eagle-import:C0603")
      (libsource (lib "eagle-import") (part "C-USC0603"))
    )
    (comp (ref "C17")
      (value "560p")
      (footprint "eagle-import:C0603")
      (libsource (lib "eagle-import") (part "C-USC0603"))
    )
    (comp (ref "C18")
      (value "560p")
      (footprint "eagle-import:C0603")
      (libsource (lib "eagle-import") (part "C-USC0603"))
    )
    (comp (ref "C19")
      (value "560p")
      (footprint "eagle-import:C0603")
      (libsource (lib "eagle-import") (part "C-USC0603"))
    )
    (comp (ref "C20")
      (value "100n")
      (footprint "eagle-import:C0603")
      (libsource (lib "eagle-import") (part "C-USC0603"))
    )
    (comp (ref "C50")
      (value "100n")
      (footprint "eagle-import:C0603")
      (libsource (lib "eagle-import") (part "C-USC0603"))
    )
    (comp (ref "C52")
      (value "100n")
      (footprint "eagle-import:C0603")
      (libsource (lib "eagle-import") (part "C-USC0603"))
    )
    (comp (ref "C53")
      (value "100n")
      (footprint "eagle-import:C0603")
      (libsource (lib "eagle-import") (part "C-USC0603"))
    )
    (comp (ref "C54")
      (value "100n")
      (footprint "eagle-import:C0603")
      (libsource (lib "eagle-import") (part "C-USC0603"))
    )
    (comp (ref "D3")
      (value "1N4148")
      (footprint "eagle-import:SOD323-W")
      (libsource (lib "eagle-import") (part "DIODE-SOD323-W"))
    )
    (comp (ref "D4")
      (value "1N4148")
      (footprint "eagle-import:SOD323-W")
      (libsource (lib "eagle-import") (part "DIODE-SOD323-W"))
    )
    (comp (ref "D5")
      (value "1N4148")
      (footprint "eagle-import:SOD323-W")
      (libsource (lib "eagle-import") (part "DIODE-SOD323-W"))
    )
    (comp (ref "D6")
      (value "1N4148")
      (footprint "eagle-import:SOD323-W")
      (libsource (lib "eagle-import") (part "DIODE-SOD323-W"))
    )
    (comp (ref "IC3")
      (value "TL072D")
      (footprint "eagle-import:SO08")
      (libsource (lib "eagle-import") (part "TL072D"))
    )
    (comp (ref "IC4")
      (value "TL074D")
      (footprint "eagle-import:SO14")
      (libsource (lib "eagle-import") (part "TL074D"))
    )
    (comp (ref "IC5")
      (value "V2164SZ")
      (footprint "eagle-import:SOIC16N")
      (libsource (lib "eagle-import") (part "SSM2164S"))
    )
    (comp (ref "J1")
      (value "PJ301_THONKICONN6")
      (footprint "eagle-import:WQP_PJ_301M6")
      (libsource (lib "eagle-import") (part "PJ301_THONKICONN6"))
    )
    (comp (ref "J2")
      (value "PJ301_THONKICONN6")
      (footprint "eagle-import:WQP_PJ_301M6")
      (libsource (lib "eagle-import") (part "PJ301_THONKICONN6"))
    )
    (comp (ref "J9")
      (value "PJ301_THONKICONN6")
      (footprint "eagle-import:WQP_PJ_301M6")
      (libsource (lib "eagle-import") (part "PJ301_THONKICONN6"))
    )
    (comp (ref "J10")
      (value "PJ301_THONKICONN6")
      (footprint "eagle-import:WQP_PJ_301M6")
      (libsource (lib "eagle-import") (part "PJ301_THONKICONN6"))
    )
    (comp (ref "J11")
      (value "PJ301_THONKICONN6")
      (footprint "eagle-import:WQP_PJ_301M6")
      (libsource (lib "eagle-import") (part "PJ301_THONKICONN6"))
    )
    (comp (ref "J12")
      (value "PJ301_THONKICONN6")
      (footprint "eagle-import:WQP_PJ_301M6")
      (libsource (lib "eagle-import") (part "PJ301_THONKICONN6"))
    )
    (comp (ref "R3")
      (value "10kB")
      (footprint "eagle-import:ALPS_POT_VERTICAL_PS")
      (libsource (lib "eagle-import") (part "POT_USVERTICAL_PS"))
    )
    (comp (ref "R4")
      (value "10kB")
      (footprint "eagle-import:ALPS_POT_VERTICAL_PS")
      (libsource (lib "eagle-import") (part "POT_USVERTICAL_PS"))
    )
    (comp (ref "R5")
      (value "100k")
      (footprint "eagle-import:R0603")
      (libsource (lib "eagle-import") (part "R-US_R0603"))
    )
    (comp (ref "R6")
      (value "100k")
      (footprint "eagle-import:R0603")
      (libsource (lib "eagle-import") (part "R-US_R0603"))
    )
    (comp (ref "R7")
      (value "100k")
      (footprint "eagle-import:R0603")
      (libsource (lib "eagle-import") (part "R-US_R0603"))
    )
    (comp (ref "R8")
      (value "100k")
      (footprint "eagle-import:R0603")
      (libsource (lib "eagle-import") (part "R-US_R0603"))
    )
    (comp (ref "R9")
      (value "100k")
      (footprint "eagle-import:R0603")
      (libsource (lib "eagle-import") (part "R-US_R0603"))
    )
    (comp (ref "R10")
      (value "100k")
      (footprint "eagle-import:R0603")
      (libsource (lib "eagle-import") (part "R-US_R0603"))
    )
    (comp (ref "R11")
      (value "100k")
      (footprint "eagle-import:R0603")
      (libsource (lib "eagle-import") (part "R-US_R0603"))
    )
    (comp (ref "R12")
      (value "100k")
      (footprint "eagle-import:R0603")
      (libsource (lib "eagle-import") (part "R-US_R0603"))
    )
    (comp (ref "R13")
      (value "18k")
      (footprint "eagle-import:R0603")
      (libsource (lib "eagle-import") (part "R-US_R0603"))
    )
    (comp (ref "R14")
      (value "18k")
      (footprint "eagle-import:R0603")
      (libsource (lib "eagle-import") (part "R-US_R0603"))
    )
    (comp (ref "R15")
      (value "100k")
      (footprint "eagle-import:R0603")
      (libsource (lib "eagle-import") (part "R-US_R0603"))
    )
    (comp (ref "R16")
      (value "100k")
      (footprint "eagle-import:R0603")
      (libsource (lib "eagle-import") (part "R-US_R0603"))
    )
    (comp (ref "R17")
      (value "100k")
      (footprint "eagle-import:R0603")
      (libsource (lib "eagle-import") (part "R-US_R0603"))
    )
    (comp (ref "R18")
      (value "100k")
      (footprint "eagle-import:R0603")
      (libsource (lib "eagle-import") (part "R-US_R0603"))
    )
    (comp (ref "R19")
      (value "100k")
      (footprint "eagle-import:R0603")
      (libsource (lib "eagle-import") (part "R-US_R0603"))
    )
    (comp (ref "R20")
      (value "510")
      (footprint "eagle-import:R0603")
      (libsource (lib "eagle-import") (part "R-US_R0603"))
    )
    (comp (ref "R21")
      (value "510")
      (footprint "eagle-import:R0603")
      (libsource (lib "eagle-import") (part "R-US_R0603"))
    )
    (comp (ref "R22")
      (value "12k")
      (footprint "eagle-import:R0603")
      (libsource (lib "eagle-import") (part "R-US_R0603"))
    )
    (comp (ref "R23")
      (value "12k")
      (footprint "eagle-import:R0603")
      (libsource (lib "eagle-import") (part "R-US_R0603"))
    )
    (comp (ref "R24")
      (value "510")
      (footprint "eagle-import:R0603")
      (libsource (lib "eagle-import") (part "R-US_R0603"))
    )
    (comp (ref "R25")
      (value "510")
      (footprint "eagle-import:R0603")
      (libsource (lib "eagle-import") (part "R-US_R0603"))
    )
    (comp (ref "R26")
      (value "120k")
      (footprint "eagle-import:R0603")
      (libsource (lib "eagle-import") (part "R-US_R0603"))
    )
    (comp (ref "R27")
      (value "120k")
      (footprint "eagle-import:R0603")
      (libsource (lib "eagle-import") (part "R-US_R0603"))
    )
    (comp (ref "R28")
      (value "200k")
      (footprint "eagle-import:R0603")
      (libsource (lib "eagle-import") (part "R-US_R0603"))
    )
    (comp (ref "R29")
      (value "200k")
      (footprint "eagle-import:R0603")
      (libsource (lib "eagle-import") (part "R-US_R0603"))
    )
    (comp (ref "R30")
      (value "120k")
      (footprint "eagle-import:R0603")
      (libsource (lib "eagle-import") (part "R-US_R0603"))
    )
    (comp (ref "R31")
      (value "120k")
      (footprint "eagle-import:R0603")
      (libsource (lib "eagle-import") (part "R-US_R0603"))
    )
    (comp (ref "R32")
      (value "100k")
      (footprint "eagle-import:R0603")
      (libsource (lib "eagle-import") (part "R-US_R0603"))
    )
    (comp (ref "R33")
      (value "100k")
      (footprint "eagle-import:R0603")
      (libsource (lib "eagle-import") (part "R-US_R0603"))
    )
    (comp (ref "R100")
      (value "10kB")
      (footprint "eagle-import:ALPS_POT_VERTICAL_PS")
      (libsource (lib "eagle-import") (part "POT_USVERTICAL_PS"))
    )
    (comp (ref "R101")
      (value "10kB")
      (footprint "eagle-import:ALPS_POT_VERTICAL_PS")
      (libsource (lib "eagle-import") (part "POT_USVERTICAL_PS"))
    )
    (comp (ref "R108")
      (value "100k")
      (footprint "eagle-import:R0603")
      (libsource (lib "eagle-import") (part "R-US_R0603"))
    )
    (comp (ref "R109")
      (value "100k")
      (footprint "eagle-import:R0603")
      (libsource (lib "eagle-import") (part "R-US_R0603"))
    )
    (comp (ref "C36")
      (value "100n")
      (footprint "eagle-import:C0603")
      (libsource (lib "eagle-import") (part "C-USC0603"))
    )
    (comp (ref "C37")
      (value "100n")
      (footprint "eagle-import:C0603")
      (libsource (lib "eagle-import") (part "C-USC0603"))
    )
    (comp (ref "C38")
      (value "560p")
      (footprint "eagle-import:C0603")
      (libsource (lib "eagle-import") (part "C-USC0603"))
    )
    (comp (ref "C39")
      (value "560p")
      (footprint "eagle-import:C0603")
      (libsource (lib "eagle-import") (part "C-USC0603"))
    )
    (comp (ref "C40")
      (value "68p")
      (footprint "eagle-import:C0603")
      (libsource (lib "eagle-import") (part "C-USC0603"))
    )
    (comp (ref "C41")
      (value "68p")
      (footprint "eagle-import:C0603")
      (libsource (lib "eagle-import") (part "C-USC0603"))
    )
    (comp (ref "C42")
      (value "100n")
      (footprint "eagle-import:C0603")
      (libsource (lib "eagle-import") (part "C-USC0603"))
    )
    (comp (ref "C43")
      (value "100n")
      (footprint "eagle-import:C0603")
      (libsource (lib "eagle-import") (part "C-USC0603"))
    )
    (comp (ref "C44")
      (value "100n")
      (footprint "eagle-import:C0603")
      (libsource (lib "eagle-import") (part "C-USC0603"))
    )
    (comp (ref "C45")
      (value "560p")
      (footprint "eagle-import:C0603")
      (libsource (lib "eagle-import") (part "C-USC0603"))
    )
    (comp (ref "C46")
      (value "560p")
      (footprint "eagle-import:C0603")
      (libsource (lib "eagle-import") (part "C-USC0603"))
    )
    (comp (ref "C47")
      (value "560p")
      (footprint "eagle-import:C0603")
      (libsource (lib "eagle-import") (part "C-USC0603"))
    )
    (comp (ref "C48")
      (value "560p")
      (footprint "eagle-import:C0603")
      (libsource (lib "eagle-import") (part "C-USC0603"))
    )
    (comp (ref "C49")
      (value "560p")
      (footprint "eagle-import:C0603")
      (libsource (lib "eagle-import") (part "C-USC0603"))
    )
    (comp (ref "C51")
      (value "100n")
      (footprint "eagle-import:C0603")
      (libsource (lib "eagle-import") (part "C-USC0603"))
    )
    (comp (ref "D10")
      (value "1N4148")
      (footprint "eagle-import:SOD323-W")
      (libsource (lib "eagle-import") (part "DIODE-SOD323-W"))
    )
    (comp (ref "D11")
      (value "1N4148")
      (footprint "eagle-import:SOD323-W")
      (libsource (lib "eagle-import") (part "DIODE-SOD323-W"))
    )
    (comp (ref "D12")
      (value "1N4148")
      (footprint "eagle-import:SOD323-W")
      (libsource (lib "eagle-import") (part "DIODE-SOD323-W"))
    )
    (comp (ref "D16")
      (value "1N4148")
      (footprint "eagle-import:SOD323-W")
      (libsource (lib "eagle-import") (part "DIODE-SOD323-W"))
    )
    (comp (ref "IC9")
      (value "TL074D")
      (footprint "eagle-import:SO14")
      (libsource (lib "eagle-import") (part "TL074D"))
    )
    (comp (ref "IC10")
      (value "TL074D")
      (footprint "eagle-import:SO14")
      (libsource (lib "eagle-import") (part "TL074D"))
    )
    (comp (ref "IC11")
      (value "V2164SZ")
      (footprint "eagle-import:SOIC16N")
      (libsource (lib "eagle-import") (part "SSM2164S"))
    )
    (comp (ref "J6")
      (value "PJ301_THONKICONN6")
      (footprint "eagle-import:WQP_PJ_301M6")
      (libsource (lib "eagle-import") (part "PJ301_THONKICONN6"))
    )
    (comp (ref "J7")
      (value "PJ301_THONKICONN6")
      (footprint "eagle-import:WQP_PJ_301M6")
      (libsource (lib "eagle-import") (part "PJ301_THONKICONN6"))
    )
    (comp (ref "J8")
      (value "PJ301_THONKICONN6")
      (footprint "eagle-import:WQP_PJ_301M6")
      (libsource (lib "eagle-import") (part "PJ301_THONKICONN6"))
    )
    (comp (ref "JP6")
      (value "M03PTH")
      (footprint "eagle-import:1X03")
      (libsource (lib "eagle-import") (part "M03PTH"))
    )
    (comp (ref "JP13")
      (value "M03PTH")
      (footprint "eagle-import:1X03")
      (libsource (lib "eagle-import") (part "M03PTH"))
    )
    (comp (ref "R65")
      (value "10kB")
      (footprint "eagle-import:ALPS_POT_VERTICAL")
      (libsource (lib "eagle-import") (part "POT_USVERTICAL"))
    )
    (comp (ref "R68")
      (value "10kB")
      (footprint "eagle-import:ALPS_POT_VERTICAL_PS")
      (libsource (lib "eagle-import") (part "POT_USVERTICAL_PS"))
    )
    (comp (ref "R69")
      (value "10kB")
      (footprint "eagle-import:ALPS_POT_VERTICAL_PS")
      (libsource (lib "eagle-import") (part "POT_USVERTICAL_PS"))
    )
    (comp (ref "R70")
      (value "200k")
      (footprint "eagle-import:R0603")
      (libsource (lib "eagle-import") (part "R-US_R0603"))
    )
    (comp (ref "R71")
      (value "100k")
      (footprint "eagle-import:R0603")
      (libsource (lib "eagle-import") (part "R-US_R0603"))
    )
    (comp (ref "R72")
      (value "100k")
      (footprint "eagle-import:R0603")
      (libsource (lib "eagle-import") (part "R-US_R0603"))
    )
    (comp (ref "R73")
      (value "100k")
      (footprint "eagle-import:R0603")
      (libsource (lib "eagle-import") (part "R-US_R0603"))
    )
    (comp (ref "R74")
      (value "100k")
      (footprint "eagle-import:R0603")
      (libsource (lib "eagle-import") (part "R-US_R0603"))
    )
    (comp (ref "R75")
      (value "100k")
      (footprint "eagle-import:R0603")
      (libsource (lib "eagle-import") (part "R-US_R0603"))
    )
    (comp (ref "R76")
      (value "100k")
      (footprint "eagle-import:R0603")
      (libsource (lib "eagle-import") (part "R-US_R0603"))
    )
    (comp (ref "R77")
      (value "100k")
      (footprint "eagle-import:R0603")
      (libsource (lib "eagle-import") (part "R-US_R0603"))
    )
    (comp (ref "R78")
      (value "120k")
      (footprint "eagle-import:R0603")
      (libsource (lib "eagle-import") (part "R-US_R0603"))
    )
    (comp (ref "R79")
      (value "120k")
      (footprint "eagle-import:R0603")
      (libsource (lib "eagle-import") (part "R-US_R0603"))
    )
    (comp (ref "R80")
      (value "200k")
      (footprint "eagle-import:R0603")
      (libsource (lib "eagle-import") (part "R-US_R0603"))
    )
    (comp (ref "R81")
      (value "100k")
      (footprint "eagle-import:R0603")
      (libsource (lib "eagle-import") (part "R-US_R0603"))
    )
    (comp (ref "R82")
      (value "100k")
      (footprint "eagle-import:R0603")
      (libsource (lib "eagle-import") (part "R-US_R0603"))
    )
    (comp (ref "R83")
      (value "100k")
      (footprint "eagle-import:R0603")
      (libsource (lib "eagle-import") (part "R-US_R0603"))
    )
    (comp (ref "R84")
      (value "12k")
      (footprint "eagle-import:R0603")
      (libsource (lib "eagle-import") (part "R-US_R0603"))
    )
    (comp (ref "R85")
      (value "18k")
      (footprint "eagle-import:R0603")
      (libsource (lib "eagle-import") (part "R-US_R0603"))
    )
    (comp (ref "R86")
      (value "100k")
      (footprint "eagle-import:R0603")
      (libsource (lib "eagle-import") (part "R-US_R0603"))
    )
    (comp (ref "R87")
      (value "100k")
      (footprint "eagle-import:R0603")
      (libsource (lib "eagle-import") (part "R-US_R0603"))
    )
    (comp (ref "R88")
      (value "100k")
      (footprint "eagle-import:R0603")
      (libsource (lib "eagle-import") (part "R-US_R0603"))
    )
    (comp (ref "R89")
      (value "510")
      (footprint "eagle-import:R0603")
      (libsource (lib "eagle-import") (part "R-US_R0603"))
    )
    (comp (ref "R90")
      (value "510")
      (footprint "eagle-import:R0603")
      (libsource (lib "eagle-import") (part "R-US_R0603"))
    )
    (comp (ref "R91")
      (value "100k")
      (footprint "eagle-import:R0603")
      (libsource (lib "eagle-import") (part "R-US_R0603"))
    )
    (comp (ref "R92")
      (value "100k")
      (footprint "eagle-import:R0603")
      (libsource (lib "eagle-import") (part "R-US_R0603"))
    )
    (comp (ref "R93")
      (value "22k")
      (footprint "eagle-import:R0603")
      (libsource (lib "eagle-import") (part "R-US_R0603"))
    )
    (comp (ref "R94")
      (value "510")
      (footprint "eagle-import:R0603")
      (libsource (lib "eagle-import") (part "R-US_R0603"))
    )
    (comp (ref "R95")
      (value "150k")
      (footprint "eagle-import:R0603")
      (libsource (lib "eagle-import") (part "R-US_R0603"))
    )
    (comp (ref "R96")
      (value "1.5M")
      (footprint "eagle-import:R0603")
      (libsource (lib "eagle-import") (part "R-US_R0603"))
    )
    (comp (ref "R97")
      (value "510")
      (footprint "eagle-import:R0603")
      (libsource (lib "eagle-import") (part "R-US_R0603"))
    )
    (comp (ref "R98")
      (value "100k")
      (footprint "eagle-import:R0603")
      (libsource (lib "eagle-import") (part "R-US_R0603"))
    )
    (comp (ref "R99")
      (value "100k")
      (footprint "eagle-import:R0603")
      (libsource (lib "eagle-import") (part "R-US_R0603"))
    )
  )
  (nets
    (net (code "1") (name "AREF_+10") (class "Default")
      (node (ref "C3") (pin "1") (pinfunction "1_1") (pintype "passive"))
      (node (ref "IC1") (pin "1") (pinfunction "C_1") (pintype "passive"))
      (node (ref "R1") (pin "2") (pinfunction "2_2") (pintype "passive"))
      (node (ref "R118") (pin "2") (pinfunction "2_2") (pintype "passive"))
      (node (ref "R121") (pin "2") (pinfunction "2_2") (pintype "passive"))
      (node (ref "R28") (pin "1") (pinfunction "1_1") (pintype "passive"))
      (node (ref "R29") (pin "1") (pinfunction "1_1") (pintype "passive"))
      (node (ref "R46") (pin "1") (pinfunction "1_1") (pintype "passive"))
      (node (ref "R63") (pin "1") (pinfunction "1_1") (pintype "passive"))
      (node (ref "R80") (pin "1") (pinfunction "1_1") (pintype "passive"))
      (node (ref "R96") (pin "1") (pinfunction "1_1") (pintype "passive"))
    )
    (net (code "2") (name "AREF_-10") (class "Default")
      (node (ref "C4") (pin "1") (pinfunction "1_1") (pintype "passive"))
      (node (ref "IC2") (pin "2") (pinfunction "A_2") (pintype "passive"))
      (node (ref "R108") (pin "1") (pinfunction "1_1") (pintype "passive"))
      (node (ref "R109") (pin "1") (pinfunction "1_1") (pintype "passive"))
      (node (ref "R12") (pin "1") (pinfunction "1_1") (pintype "passive"))
      (node (ref "R2") (pin "2") (pinfunction "2_2") (pintype "passive"))
      (node (ref "R43") (pin "1") (pinfunction "1_1") (pintype "passive"))
      (node (ref "R49") (pin "1") (pinfunction "1_1") (pintype "passive"))
      (node (ref "R5") (pin "1") (pinfunction "1_1") (pintype "passive"))
      (node (ref "R54") (pin "1") (pinfunction "1_1") (pintype "passive"))
      (node (ref "R70") (pin "1") (pinfunction "1_1") (pintype "passive"))
      (node (ref "R77") (pin "1") (pinfunction "1_1") (pintype "passive"))
      (node (ref "R83") (pin "1") (pinfunction "1_1") (pintype "passive"))
    )
    (net (code "3") (name "BP_1") (class "Default")
      (node (ref "C40") (pin "2") (pinfunction "2_2") (pintype "passive"))
      (node (ref "IC9") (pin "7") (pinfunction "OUT_7") (pintype "output"))
      (node (ref "JP13") (pin "1") (pinfunction "1_1") (pintype "passive"))
      (node (ref "R87") (pin "1") (pinfunction "1_1") (pintype "passive"))
      (node (ref "R98") (pin "1") (pinfunction "1_1") (pintype "passive"))
    )
    (net (code "4") (name "BP_2") (class "Default")
      (node (ref "C25") (pin "2") (pinfunction "2_2") (pintype "passive"))
      (node (ref "IC6") (pin "7") (pinfunction "OUT_7") (pintype "output"))
      (node (ref "JP5") (pin "1") (pinfunction "1_1") (pintype "passive"))
      (node (ref "R53") (pin "1") (pinfunction "1_1") (pintype "passive"))
      (node (ref "R66") (pin "1") (pinfunction "1_1") (pintype "passive"))
    )
    (net (code "5") (name "F_GLOBAL") (class "Default")
      (node (ref "J11") (pin "P3") (pinfunction "3_P3") (pintype "passive"))
      (node (ref "R47") (pin "1") (pinfunction "1_1") (pintype "passive"))
      (node (ref "R7") (pin "1") (pinfunction "1_1") (pintype "passive"))
      (node (ref "R8") (pin "1") (pinfunction "1_1") (pintype "passive"))
      (node (ref "R81") (pin "1") (pinfunction "1_1") (pintype "passive"))
    )
    (net (code "6") (name "GAIN_GLOBAL") (class "Default")
      (node (ref "J12") (pin "P3") (pinfunction "3_P3") (pintype "passive"))
      (node (ref "R26") (pin "1") (pinfunction "1_1") (pintype "passive"))
      (node (ref "R31") (pin "1") (pinfunction "1_1") (pintype "passive"))
      (node (ref "R44") (pin "1") (pinfunction "1_1") (pintype "passive"))
      (node (ref "R79") (pin "1") (pinfunction "1_1") (pintype "passive"))
    )
    (net (code "7") (name "GND") (class "Default")
      (node (ref "C1") (pin "-") (pinfunction "-_-") (pintype "passive"))
      (node (ref "C12") (pin "2") (pinfunction "2_2") (pintype "passive"))
      (node (ref "C13") (pin "1") (pinfunction "1_1") (pintype "passive"))
      (node (ref "C14") (pin "2") (pinfunction "2_2") (pintype "passive"))
      (node (ref "C15") (pin "2") (pinfunction "2_2") (pintype "passive"))
      (node (ref "C18") (pin "2") (pinfunction "2_2") (pintype "passive"))
      (node (ref "C19") (pin "2") (pinfunction "2_2") (pintype "passive"))
      (node (ref "C2") (pin "+") (pinfunction "+_+") (pintype "passive"))
      (node (ref "C20") (pin "1") (pinfunction "1_1") (pintype "passive"))
      (node (ref "C21") (pin "2") (pinfunction "2_2") (pintype "passive"))
      (node (ref "C22") (pin "1") (pinfunction "1_1") (pintype "passive"))
      (node (ref "C27") (pin "2") (pinfunction "2_2") (pintype "passive"))
      (node (ref "C28") (pin "1") (pinfunction "1_1") (pintype "passive"))
      (node (ref "C29") (pin "2") (pinfunction "2_2") (pintype "passive"))
      (node (ref "C3") (pin "2") (pinfunction "2_2") (pintype "passive"))
      (node (ref "C30") (pin "2") (pinfunction "2_2") (pintype "passive"))
      (node (ref "C31") (pin "2") (pinfunction "2_2") (pintype "passive"))
      (node (ref "C33") (pin "2") (pinfunction "2_2") (pintype "passive"))
      (node (ref "C34") (pin "2") (pinfunction "2_2") (pintype "passive"))
      (node (ref "C35") (pin "1") (pinfunction "1_1") (pintype "passive"))
      (node (ref "C36") (pin "2") (pinfunction "2_2") (pintype "passive"))
      (node (ref "C37") (pin "1") (pinfunction "1_1") (pintype "passive"))
      (node (ref "C4") (pin "2") (pinfunction "2_2") (pintype "passive"))
      (node (ref "C42") (pin "2") (pinfunction "2_2") (pintype "passive"))
      (node (ref "C43") (pin "2") (pinfunction "2_2") (pintype "passive"))
      (node (ref "C44") (pin "1") (pinfunction "1_1") (pintype "passive"))
      (node (ref "C45") (pin "2") (pinfunction "2_2") (pintype "passive"))
      (node (ref "C47") (pin "2") (pinfunction "2_2") (pintype "passive"))
      (node (ref "C48") (pin "2") (pinfunction "2_2") (pintype "passive"))
      (node (ref "C49") (pin "2") (pinfunction "2_2") (pintype "passive"))
      (node (ref "C5") (pin "2") (pinfunction "2_2") (pintype "passive"))
      (node (ref "C50") (pin "2") (pinfunction "2_2") (pintype "passive"))
      (node (ref "C51") (pin "1") (pinfunction "1_1") (pintype "passive"))
      (node (ref "C52") (pin "2") (pinfunction "2_2") (pintype "passive"))
      (node (ref "C53") (pin "1") (pinfunction "1_1") (pintype "passive"))
      (node (ref "C54") (pin "1") (pinfunction "1_1") (pintype "passive"))
      (node (ref "C55") (pin "2") (pinfunction "2_2") (pintype "passive"))
      (node (ref "C56") (pin "2") (pinfunction "2_2") (pintype "passive"))
      (node (ref "C58") (pin "-") (pinfunction "-_-") (pintype "passive"))
      (node (ref "C8") (pin "1") (pinfunction "1_1") (pintype "passive"))
      (node (ref "C9") (pin "2") (pinfunction "2_2") (pintype "passive"))
      (node (ref "D1") (pin "C") (pinfunction "C_C") (pintype "passive"))
      (node (ref "D10") (pin "A") (pinfunction "A_A") (pintype "passive"))
      (node (ref "D12") (pin "A") (pinfunction "A_A") (pintype "passive"))
      (node (ref "D3") (pin "A") (pinfunction "A_A") (pintype "passive"))
      (node (ref "D4") (pin "A") (pinfunction "A_A") (pintype "passive"))
      (node (ref "D5") (pin "A") (pinfunction "A_A") (pintype "passive"))
      (node (ref "D6") (pin "A") (pinfunction "A_A") (pintype "passive"))
      (node (ref "D7") (pin "A") (pinfunction "A_A") (pintype "passive"))
      (node (ref "D9") (pin "A") (pinfunction "A_A") (pintype "passive"))
      (node (ref "IC1") (pin "2") (pinfunction "A_2") (pintype "passive"))
      (node (ref "IC10") (pin "10") (pinfunction "+IN_10") (pintype "input"))
      (node (ref "IC10") (pin "12") (pinfunction "+IN_12") (pintype "input"))
      (node (ref "IC10") (pin "3") (pinfunction "+IN_3") (pintype "input"))
      (node (ref "IC10") (pin "5") (pinfunction "+IN_5") (pintype "input"))
      (node (ref "IC11") (pin "8") (pinfunction "GND_8") (pintype "power_in"))
      (node (ref "IC12") (pin "3") (pinfunction "+IN_3") (pintype "input"))
      (node (ref "IC12") (pin "5") (pinfunction "+IN_5") (pintype "input"))
      (node (ref "IC13") (pin "3") (pinfunction "+IN_3") (pintype "input"))
      (node (ref "IC13") (pin "5") (pinfunction "+IN_5") (pintype "input"))
      (node (ref "IC14") (pin "4") (pinfunction "V-_4") (pintype "power_in"))
      (node (ref "IC2") (pin "1") (pinfunction "C_1") (pintype "passive"))
      (node (ref "IC3") (pin "3") (pinfunction "+IN_3") (pintype "input"))
      (node (ref "IC3") (pin "5") (pinfunction "+IN_5") (pintype "input"))
      (node (ref "IC4") (pin "10") (pinfunction "+IN_10") (pintype "input"))
      (node (ref "IC4") (pin "12") (pinfunction "+IN_12") (pintype "input"))
      (node (ref "IC4") (pin "3") (pinfunction "+IN_3") (pintype "input"))
      (node (ref "IC4") (pin "5") (pinfunction "+IN_5") (pintype "input"))
      (node (ref "IC5") (pin "8") (pinfunction "GND_8") (pintype "power_in"))
      (node (ref "IC6") (pin "10") (pinfunction "+IN_10") (pintype "input"))
      (node (ref "IC6") (pin "12") (pinfunction "+IN_12") (pintype "input"))
      (node (ref "IC6") (pin "3") (pinfunction "+IN_3") (pintype "input"))
      (node (ref "IC6") (pin "5") (pinfunction "+IN_5") (pintype "input"))
      (node (ref "IC7") (pin "10") (pinfunction "+IN_10") (pintype "input"))
      (node (ref "IC7") (pin "12") (pinfunction "+IN_12") (pintype "input"))
      (node (ref "IC7") (pin "3") (pinfunction "+IN_3") (pintype "input"))
      (node (ref "IC7") (pin "5") (pinfunction "+IN_5") (pintype "input"))
      (node (ref "IC8") (pin "8") (pinfunction "GND_8") (pintype "power_in"))
      (node (ref "IC9") (pin "10") (pinfunction "+IN_10") (pintype "input"))
      (node (ref "IC9") (pin "12") (pinfunction "+IN_12") (pintype "input"))
      (node (ref "IC9") (pin "3") (pinfunction "+IN_3") (pintype "input"))
      (node (ref "IC9") (pin "5") (pinfunction "+IN_5") (pintype "input"))
      (node (ref "J1") (pin "P1") (pinfunction "1_P1") (pintype "passive"))
      (node (ref "J10") (pin "P1") (pinfunction "1_P1") (pintype "passive"))
      (node (ref "J11") (pin "P1") (pinfunction "1_P1") (pintype "passive"))
      (node (ref "J12") (pin "P1") (pinfunction "1_P1") (pintype "passive"))
      (node (ref "J13") (pin "P1") (pinfunction "1_P1") (pintype "passive"))
      (node (ref "J14") (pin "P1") (pinfunction "1_P1") (pintype "passive"))
      (node (ref "J2") (pin "P1") (pinfunction "1_P1") (pintype "passive"))
      (node (ref "J3") (pin "P1") (pinfunction "1_P1") (pintype "passive"))
      (node (ref "J4") (pin "P1") (pinfunction "1_P1") (pintype "passive"))
      (node (ref "J5") (pin "P1") (pinfunction "1_P1") (pintype "passive"))
      (node (ref "J6") (pin "P1") (pinfunction "1_P1") (pintype "passive"))
      (node (ref "J7") (pin "P1") (pinfunction "1_P1") (pintype "passive"))
      (node (ref "J8") (pin "P1") (pinfunction "1_P1") (pintype "passive"))
      (node (ref "J9") (pin "P1") (pinfunction "1_P1") (pintype "passive"))
      (node (ref "JP11") (pin "3") (pinfunction "3_3") (pintype "passive"))
      (node (ref "JP11") (pin "4") (pinfunction "4_4") (pintype "passive"))
      (node (ref "JP11") (pin "5") (pinfunction "5_5") (pintype "passive"))
      (node (ref "JP11") (pin "6") (pinfunction "6_6") (pintype "passive"))
      (node (ref "JP11") (pin "7") (pinfunction "7_7") (pintype "passive"))
      (node (ref "JP11") (pin "8") (pinfunction "8_8") (pintype "passive"))
      (node (ref "JP6") (pin "1") (pinfunction "1_1") (pintype "passive"))
      (node (ref "JP6") (pin "2") (pinfunction "2_2") (pintype "passive"))
      (node (ref "JP6") (pin "3") (pinfunction "3_3") (pintype "passive"))
      (node (ref "JP7") (pin "1") (pinfunction "1_1") (pintype "passive"))
      (node (ref "JP7") (pin "2") (pinfunction "2_2") (pintype "passive"))
      (node (ref "JP7") (pin "3") (pinfunction "3_3") (pintype "passive"))
      (node (ref "Q1") (pin "E") (pinfunction "E_E") (pintype "passive"))
      (node (ref "R100") (pin "P$1") (pinfunction "E_P$1") (pintype "passive"))
      (node (ref "R101") (pin "P$1") (pinfunction "E_P$1") (pintype "passive"))
      (node (ref "R116") (pin "1") (pinfunction "1_1") (pintype "passive"))
      (node (ref "R117") (pin "1") (pinfunction "1_1") (pintype "passive"))
      (node (ref "R120") (pin "1") (pinfunction "1_1") (pintype "passive"))
      (node (ref "R3") (pin "P$1") (pinfunction "E_P$1") (pintype "passive"))
      (node (ref "R34") (pin "P$1") (pinfunction "E_P$1") (pintype "passive"))
      (node (ref "R36") (pin "P$1") (pinfunction "E_P$1") (pintype "passive"))
      (node (ref "R4") (pin "P$1") (pinfunction "E_P$1") (pintype "passive"))
      (node (ref "R42") (pin "P$3") (pinfunction "A_P$3") (pintype "passive"))
      (node (ref "R65") (pin "P$3") (pinfunction "A_P$3") (pintype "passive"))
      (node (ref "R68") (pin "P$1") (pinfunction "E_P$1") (pintype "passive"))
      (node (ref "R69") (pin "P$1") (pinfunction "E_P$1") (pintype "passive"))
    )
    (net (code "8") (name "HP_1") (class "Default")
      (node (ref "IC9") (pin "1") (pinfunction "OUT_1") (pintype "output"))
      (node (ref "JP13") (pin "3") (pinfunction "3_3") (pintype "passive"))
      (node (ref "R75") (pin "2") (pinfunction "2_2") (pintype "passive"))
      (node (ref "R86") (pin "1") (pinfunction "1_1") (pintype "passive"))
    )
    (net (code "9") (name "HP_2") (class "Default")
      (node (ref "IC6") (pin "1") (pinfunction "OUT_1") (pintype "output"))
      (node (ref "JP5") (pin "3") (pinfunction "3_3") (pintype "passive"))
      (node (ref "R40") (pin "2") (pinfunction "2_2") (pintype "passive"))
      (node (ref "R52") (pin "1") (pinfunction "1_1") (pintype "passive"))
    )
    (net (code "10") (name "IN") (class "Default")
      (node (ref "IC12") (pin "7") (pinfunction "OUT_7") (pintype "output"))
      (node (ref "JP12") (pin "3") (pinfunction "3_3") (pintype "passive"))
      (node (ref "R103") (pin "2") (pinfunction "2_2") (pintype "passive"))
      (node (ref "R15") (pin "1") (pinfunction "1_1") (pintype "passive"))
      (node (ref "R16") (pin "1") (pinfunction "1_1") (pintype "passive"))
      (node (ref "R17") (pin "1") (pinfunction "1_1") (pintype "passive"))
      (node (ref "R37") (pin "1") (pinfunction "1_1") (pintype "passive"))
      (node (ref "R72") (pin "1") (pinfunction "1_1") (pintype "passive"))
    )
    (net (code "11") (name "MINUS_BUS") (class "Default")
      (node (ref "IC11") (pin "12") (pinfunction "OUT_12") (pintype "output"))
      (node (ref "IC13") (pin "2") (pinfunction "-IN_2") (pintype "input"))
      (node (ref "IC5") (pin "5") (pinfunction "OUT_5") (pintype "output"))
      (node (ref "IC8") (pin "12") (pinfunction "OUT_12") (pintype "output"))
      (node (ref "R104") (pin "2") (pinfunction "2_2") (pintype "passive"))
      (node (ref "R107") (pin "1") (pinfunction "1_1") (pintype "passive"))
      (node (ref "R19") (pin "2") (pinfunction "2_2") (pintype "passive"))
    )
    (net (code "12") (name "Net-(C14-Pad1)") (class "Default")
      (node (ref "C14") (pin "1") (pinfunction "1_1") (pintype "passive"))
      (node (ref "R21") (pin "1") (pinfunction "1_1") (pintype "passive"))
    )
    (net (code "13") (name "Net-(C15-Pad1)") (class "Default")
      (node (ref "C15") (pin "1") (pinfunction "1_1") (pintype "passive"))
      (node (ref "R20") (pin "1") (pinfunction "1_1") (pintype "passive"))
    )
    (net (code "14") (name "Net-(C18-Pad1)") (class "Default")
      (node (ref "C18") (pin "1") (pinfunction "1_1") (pintype "passive"))
      (node (ref "R24") (pin "1") (pinfunction "1_1") (pintype "passive"))
    )
    (net (code "15") (name "Net-(C19-Pad1)") (class "Default")
      (node (ref "C19") (pin "1") (pinfunction "1_1") (pintype "passive"))
      (node (ref "R25") (pin "1") (pinfunction "1_1") (pintype "passive"))
    )
    (net (code "16") (name "Net-(C29-Pad1)") (class "Default")
      (node (ref "C29") (pin "1") (pinfunction "1_1") (pintype "passive"))
      (node (ref "R56") (pin "1") (pinfunction "1_1") (pintype "passive"))
    )
    (net (code "17") (name "Net-(C30-Pad1)") (class "Default")
      (node (ref "C30") (pin "1") (pinfunction "1_1") (pintype "passive"))
      (node (ref "R57") (pin "1") (pinfunction "1_1") (pintype "passive"))
    )
    (net (code "18") (name "Net-(C33-Pad1)") (class "Default")
      (node (ref "C33") (pin "1") (pinfunction "1_1") (pintype "passive"))
      (node (ref "R61") (pin "1") (pinfunction "1_1") (pintype "passive"))
    )
    (net (code "19") (name "Net-(C34-Pad1)") (class "Default")
      (node (ref "C34") (pin "1") (pinfunction "1_1") (pintype "passive"))
      (node (ref "R64") (pin "1") (pinfunction "1_1") (pintype "passive"))
    )
    (net (code "20") (name "Net-(C45-Pad1)") (class "Default")
      (node (ref "C45") (pin "1") (pinfunction "1_1") (pintype "passive"))
      (node (ref "R89") (pin "1") (pinfunction "1_1") (pintype "passive"))
    )
    (net (code "21") (name "Net-(C47-Pad1)") (class "Default")
      (node (ref "C47") (pin "1") (pinfunction "1_1") (pintype "passive"))
      (node (ref "R90") (pin "1") (pinfunction "1_1") (pintype "passive"))
    )
    (net (code "22") (name "Net-(C48-Pad1)") (class "Default")
      (node (ref "C48") (pin "1") (pinfunction "1_1") (pintype "passive"))
      (node (ref "R94") (pin "1") (pinfunction "1_1") (pintype "passive"))
    )
    (net (code "23") (name "Net-(C49-Pad1)") (class "Default")
      (node (ref "C49") (pin "1") (pinfunction "1_1") (pintype "passive"))
      (node (ref "R97") (pin "1") (pinfunction "1_1") (pintype "passive"))
    )
    (net (code "24") (name "Net-(C55-Pad1)") (class "Default")
      (node (ref "C55") (pin "1") (pinfunction "1_1") (pintype "passive"))
      (node (ref "R113") (pin "2") (pinfunction "2_2") (pintype "passive"))
      (node (ref "R114") (pin "1") (pinfunction "1_1") (pintype "passive"))
    )
    (net (code "25") (name "Net-(C57-Pad1)") (class "Default")
      (node (ref "C57") (pin "1") (pinfunction "1_1") (pintype "passive"))
      (node (ref "R115") (pin "1") (pinfunction "1_1") (pintype "passive"))
    )
    (net (code "26") (name "Net-(D2-PadA)") (class "Default")
      (node (ref "D2") (pin "A") (pinfunction "A_A") (pintype "passive"))
      (node (ref "JP11") (pin "1") (pinfunction "1_1") (pintype "passive"))
      (node (ref "JP11") (pin "2") (pinfunction "2_2") (pintype "passive"))
    )
    (net (code "27") (name "Net-(D13-PadC)") (class "Default")
      (node (ref "D13") (pin "C") (pinfunction "C_C") (pintype "passive"))
      (node (ref "D14") (pin "C") (pinfunction "C_C") (pintype "passive"))
      (node (ref "R113") (pin "1") (pinfunction "1_1") (pintype "passive"))
    )
    (net (code "28") (name "Net-(IC3A--IN)") (class "Default")
      (node (ref "C6") (pin "1") (pinfunction "1_1") (pintype "passive"))
      (node (ref "IC3") (pin "2") (pinfunction "-IN_2") (pintype "input"))
      (node (ref "IC5") (pin "4") (pinfunction "OUT_4") (pintype "output"))
    )
    (net (code "29") (name "Net-(IC3A-OUT)") (class "Default")
      (node (ref "C6") (pin "2") (pinfunction "2_2") (pintype "passive"))
      (node (ref "IC3") (pin "1") (pinfunction "OUT_1") (pintype "output"))
      (node (ref "R11") (pin "2") (pinfunction "2_2") (pintype "passive"))
      (node (ref "R32") (pin "1") (pinfunction "1_1") (pintype "passive"))
      (node (ref "R33") (pin "1") (pinfunction "1_1") (pintype "passive"))
    )
    (net (code "30") (name "Net-(IC3B--IN)") (class "Default")
      (node (ref "C7") (pin "1") (pinfunction "1_1") (pintype "passive"))
      (node (ref "IC3") (pin "6") (pinfunction "-IN_6") (pintype "input"))
      (node (ref "IC5") (pin "13") (pinfunction "OUT_13") (pintype "output"))
    )
    (net (code "31") (name "Net-(IC3B-OUT)") (class "Default")
      (node (ref "C7") (pin "2") (pinfunction "2_2") (pintype "passive"))
      (node (ref "IC3") (pin "7") (pinfunction "OUT_7") (pintype "output"))
      (node (ref "R10") (pin "2") (pinfunction "2_2") (pintype "passive"))
      (node (ref "R18") (pin "1") (pinfunction "1_1") (pintype "passive"))
      (node (ref "R19") (pin "1") (pinfunction "1_1") (pintype "passive"))
    )
    (net (code "32") (name "Net-(IC4A--IN)") (class "Default")
      (node (ref "C10") (pin "2") (pinfunction "2_2") (pintype "passive"))
      (node (ref "IC4") (pin "2") (pinfunction "-IN_2") (pintype "input"))
      (node (ref "R13") (pin "1") (pinfunction "1_1") (pintype "passive"))
      (node (ref "R3") (pin "P$3") (pinfunction "A_P$3") (pintype "passive"))
      (node (ref "R6") (pin "2") (pinfunction "2_2") (pintype "passive"))
      (node (ref "R7") (pin "2") (pinfunction "2_2") (pintype "passive"))
    )
    (net (code "33") (name "Net-(IC4A-OUT)") (class "Default")
      (node (ref "C10") (pin "1") (pinfunction "1_1") (pintype "passive"))
      (node (ref "D3") (pin "C") (pinfunction "C_C") (pintype "passive"))
      (node (ref "IC4") (pin "1") (pinfunction "OUT_1") (pintype "output"))
      (node (ref "IC5") (pin "14") (pinfunction "CTRL_14") (pintype "input"))
      (node (ref "R13") (pin "2") (pinfunction "2_2") (pintype "passive"))
    )
    (net (code "34") (name "Net-(IC4B--IN)") (class "Default")
      (node (ref "C16") (pin "2") (pinfunction "2_2") (pintype "passive"))
      (node (ref "IC4") (pin "6") (pinfunction "-IN_6") (pintype "input"))
      (node (ref "R101") (pin "P$3") (pinfunction "A_P$3") (pintype "passive"))
      (node (ref "R22") (pin "1") (pinfunction "1_1") (pintype "passive"))
      (node (ref "R26") (pin "2") (pinfunction "2_2") (pintype "passive"))
      (node (ref "R27") (pin "2") (pinfunction "2_2") (pintype "passive"))
      (node (ref "R28") (pin "2") (pinfunction "2_2") (pintype "passive"))
    )
    (net (code "35") (name "Net-(IC4B-OUT)") (class "Default")
      (node (ref "C16") (pin "1") (pinfunction "1_1") (pintype "passive"))
      (node (ref "D6") (pin "C") (pinfunction "C_C") (pintype "passive"))
      (node (ref "IC4") (pin "7") (pinfunction "OUT_7") (pintype "output"))
      (node (ref "IC5") (pin "6") (pinfunction "CTRL_6") (pintype "input"))
      (node (ref "R22") (pin "2") (pinfunction "2_2") (pintype "passive"))
    )
    (net (code "36") (name "Net-(IC4C--IN)") (class "Default")
      (node (ref "C17") (pin "2") (pinfunction "2_2") (pintype "passive"))
      (node (ref "IC4") (pin "9") (pinfunction "-IN_9") (pintype "input"))
      (node (ref "R23") (pin "1") (pinfunction "1_1") (pintype "passive"))
      (node (ref "R29") (pin "2") (pinfunction "2_2") (pintype "passive"))
      (node (ref "R30") (pin "2") (pinfunction "2_2") (pintype "passive"))
      (node (ref "R31") (pin "2") (pinfunction "2_2") (pintype "passive"))
      (node (ref "R4") (pin "P$3") (pinfunction "A_P$3") (pintype "passive"))
    )
    (net (code "37") (name "Net-(IC4C-OUT)") (class "Default")
      (node (ref "C17") (pin "1") (pinfunction "1_1") (pintype "passive"))
      (node (ref "D5") (pin "C") (pinfunction "C_C") (pintype "passive"))
      (node (ref "IC4") (pin "8") (pinfunction "OUT_8") (pintype "output"))
      (node (ref "IC5") (pin "11") (pinfunction "CTRL_11") (pintype "input"))
      (node (ref "R23") (pin "2") (pinfunction "2_2") (pintype "passive"))
    )
    (net (code "38") (name "Net-(IC4D--IN)") (class "Default")
      (node (ref "C11") (pin "2") (pinfunction "2_2") (pintype "passive"))
      (node (ref "IC4") (pin "13") (pinfunction "-IN_13") (pintype "input"))
      (node (ref "R100") (pin "P$3") (pinfunction "A_P$3") (pintype "passive"))
      (node (ref "R14") (pin "1") (pinfunction "1_1") (pintype "passive"))
      (node (ref "R8") (pin "2") (pinfunction "2_2") (pintype "passive"))
      (node (ref "R9") (pin "2") (pinfunction "2_2") (pintype "passive"))
    )
    (net (code "39") (name "Net-(IC4D-OUT)") (class "Default")
      (node (ref "C11") (pin "1") (pinfunction "1_1") (pintype "passive"))
      (node (ref "D4") (pin "C") (pinfunction "C_C") (pintype "passive"))
      (node (ref "IC4") (pin "14") (pinfunction "OUT_14") (pintype "output"))
      (node (ref "IC5") (pin "3") (pinfunction "CTRL_3") (pintype "input"))
      (node (ref "R14") (pin "2") (pinfunction "2_2") (pintype "passive"))
    )
    (net (code "40") (name "Net-(IC5A-IN)") (class "Default")
      (node (ref "IC5") (pin "2") (pinfunction "IN_2") (pintype "input"))
      (node (ref "R11") (pin "1") (pinfunction "1_1") (pintype "passive"))
      (node (ref "R15") (pin "2") (pinfunction "2_2") (pintype "passive"))
      (node (ref "R20") (pin "2") (pinfunction "2_2") (pintype "passive"))
    )
    (net (code "41") (name "Net-(IC5B-IN)") (class "Default")
      (node (ref "IC5") (pin "7") (pinfunction "IN_7") (pintype "input"))
      (node (ref "R25") (pin "2") (pinfunction "2_2") (pintype "passive"))
      (node (ref "R32") (pin "2") (pinfunction "2_2") (pintype "passive"))
    )
    (net (code "42") (name "Net-(IC5C-IN)") (class "Default")
      (node (ref "IC5") (pin "10") (pinfunction "IN_10") (pintype "input"))
      (node (ref "R17") (pin "2") (pinfunction "2_2") (pintype "passive"))
      (node (ref "R18") (pin "2") (pinfunction "2_2") (pintype "passive"))
      (node (ref "R24") (pin "2") (pinfunction "2_2") (pintype "passive"))
    )
    (net (code "43") (name "Net-(IC5D-IN)") (class "Default")
      (node (ref "IC5") (pin "15") (pinfunction "IN_15") (pintype "input"))
      (node (ref "R10") (pin "1") (pinfunction "1_1") (pintype "passive"))
      (node (ref "R16") (pin "2") (pinfunction "2_2") (pintype "passive"))
      (node (ref "R21") (pin "2") (pinfunction "2_2") (pintype "passive"))
    )
    (net (code "44") (name "Net-(IC6A--IN)") (class "Default")
      (node (ref "IC6") (pin "2") (pinfunction "-IN_2") (pintype "input"))
      (node (ref "R35") (pin "1") (pinfunction "1_1") (pintype "passive"))
      (node (ref "R37") (pin "2") (pinfunction "2_2") (pintype "passive"))
      (node (ref "R38") (pin "1") (pinfunction "1_1") (pintype "passive"))
      (node (ref "R40") (pin "1") (pinfunction "1_1") (pintype "passive"))
    )
    (net (code "45") (name "Net-(IC6B--IN)") (class "Default")
      (node (ref "C25") (pin "1") (pinfunction "1_1") (pintype "passive"))
      (node (ref "IC6") (pin "6") (pinfunction "-IN_6") (pintype "input"))
      (node (ref "IC8") (pin "4") (pinfunction "OUT_4") (pintype "output"))
    )
    (net (code "46") (name "Net-(IC6C--IN)") (class "Default")
      (node (ref "C26") (pin "1") (pinfunction "1_1") (pintype "passive"))
      (node (ref "IC6") (pin "9") (pinfunction "-IN_9") (pintype "input"))
      (node (ref "IC8") (pin "13") (pinfunction "OUT_13") (pintype "output"))
    )
    (net (code "47") (name "Net-(IC6C-OUT)") (class "Default")
      (node (ref "C26") (pin "2") (pinfunction "2_2") (pintype "passive"))
      (node (ref "IC6") (pin "8") (pinfunction "OUT_8") (pintype "output"))
      (node (ref "JP5") (pin "2") (pinfunction "2_2") (pintype "passive"))
      (node (ref "R35") (pin "2") (pinfunction "2_2") (pintype "passive"))
    )
    (net (code "48") (name "Net-(IC6D--IN)") (class "Default")
      (node (ref "IC6") (pin "13") (pinfunction "-IN_13") (pintype "input"))
      (node (ref "IC8") (pin "5") (pinfunction "OUT_5") (pintype "output"))
      (node (ref "R41") (pin "2") (pinfunction "2_2") (pintype "passive"))
    )
    (net (code "49") (name "Net-(IC6D-OUT)") (class "Default")
      (node (ref "IC6") (pin "14") (pinfunction "OUT_14") (pintype "output"))
      (node (ref "R38") (pin "2") (pinfunction "2_2") (pintype "passive"))
      (node (ref "R39") (pin "1") (pinfunction "1_1") (pintype "passive"))
      (node (ref "R55") (pin "1") (pinfunction "1_1") (pintype "passive"))
      (node (ref "R67") (pin "1") (pinfunction "1_1") (pintype "passive"))
    )
    (net (code "50") (name "Net-(IC7A--IN)") (class "Default")
      (node (ref "C23") (pin "2") (pinfunction "2_2") (pintype "passive"))
      (node (ref "IC7") (pin "2") (pinfunction "-IN_2") (pintype "input"))
      (node (ref "R36") (pin "P$3") (pinfunction "A_P$3") (pintype "passive"))
      (node (ref "R44") (pin "2") (pinfunction "2_2") (pintype "passive"))
      (node (ref "R45") (pin "2") (pinfunction "2_2") (pintype "passive"))
      (node (ref "R46") (pin "2") (pinfunction "2_2") (pintype "passive"))
      (node (ref "R50") (pin "1") (pinfunction "1_1") (pintype "passive"))
    )
    (net (code "51") (name "Net-(IC7A-OUT)") (class "Default")
      (node (ref "C23") (pin "1") (pinfunction "1_1") (pintype "passive"))
      (node (ref "D7") (pin "C") (pinfunction "C_C") (pintype "passive"))
      (node (ref "IC7") (pin "1") (pinfunction "OUT_1") (pintype "output"))
      (node (ref "IC8") (pin "11") (pinfunction "CTRL_11") (pintype "input"))
      (node (ref "R50") (pin "2") (pinfunction "2_2") (pintype "passive"))
    )
    (net (code "52") (name "Net-(IC7B--IN)") (class "Default")
      (node (ref "IC7") (pin "6") (pinfunction "-IN_6") (pintype "input"))
      (node (ref "R58") (pin "2") (pinfunction "2_2") (pintype "passive"))
      (node (ref "R59") (pin "1") (pinfunction "1_1") (pintype "passive"))
    )
    (net (code "53") (name "Net-(IC7B-OUT)") (class "Default")
      (node (ref "IC7") (pin "7") (pinfunction "OUT_7") (pintype "output"))
      (node (ref "R59") (pin "2") (pinfunction "2_2") (pintype "passive"))
      (node (ref "R62") (pin "1") (pinfunction "1_1") (pintype "passive"))
    )
    (net (code "54") (name "Net-(IC7C--IN)") (class "Default")
      (node (ref "C32") (pin "2") (pinfunction "2_2") (pintype "passive"))
      (node (ref "IC7") (pin "9") (pinfunction "-IN_9") (pintype "input"))
      (node (ref "R42") (pin "P$1") (pinfunction "E_P$1") (pintype "passive"))
      (node (ref "R60") (pin "1") (pinfunction "1_1") (pintype "passive"))
      (node (ref "R62") (pin "2") (pinfunction "2_2") (pintype "passive"))
      (node (ref "R63") (pin "2") (pinfunction "2_2") (pintype "passive"))
    )
    (net (code "55") (name "Net-(IC7C-OUT)") (class "Default")
      (node (ref "C32") (pin "1") (pinfunction "1_1") (pintype "passive"))
      (node (ref "D9") (pin "C") (pinfunction "C_C") (pintype "passive"))
      (node (ref "IC7") (pin "8") (pinfunction "OUT_8") (pintype "output"))
      (node (ref "IC8") (pin "6") (pinfunction "CTRL_6") (pintype "input"))
      (node (ref "R60") (pin "2") (pinfunction "2_2") (pintype "passive"))
    )
    (net (code "56") (name "Net-(IC7D--IN)") (class "Default")
      (node (ref "C24") (pin "2") (pinfunction "2_2") (pintype "passive"))
      (node (ref "D8") (pin "A") (pinfunction "A_A") (pintype "passive"))
      (node (ref "IC7") (pin "13") (pinfunction "-IN_13") (pintype "input"))
      (node (ref "R34") (pin "P$3") (pinfunction "A_P$3") (pintype "passive"))
      (node (ref "R47") (pin "2") (pinfunction "2_2") (pintype "passive"))
      (node (ref "R48") (pin "2") (pinfunction "2_2") (pintype "passive"))
      (node (ref "R51") (pin "1") (pinfunction "1_1") (pintype "passive"))
    )
    (net (code "57") (name "Net-(IC7D-OUT)") (class "Default")
      (node (ref "D15") (pin "A") (pinfunction "A_A") (pintype "passive"))
      (node (ref "D8") (pin "C") (pinfunction "C_C") (pintype "passive"))
      (node (ref "IC7") (pin "14") (pinfunction "OUT_14") (pintype "output"))
    )
    (net (code "58") (name "Net-(IC8A-CTRL)") (class "Default")
      (node (ref "C24") (pin "1") (pinfunction "1_1") (pintype "passive"))
      (node (ref "D15") (pin "C") (pinfunction "C_C") (pintype "passive"))
      (node (ref "IC8") (pin "14") (pinfunction "CTRL_14") (pintype "input"))
      (node (ref "IC8") (pin "3") (pinfunction "CTRL_3") (pintype "input"))
      (node (ref "R51") (pin "2") (pinfunction "2_2") (pintype "passive"))
    )
    (net (code "59") (name "Net-(IC8A-IN)") (class "Default")
      (node (ref "IC8") (pin "2") (pinfunction "IN_2") (pintype "input"))
      (node (ref "R52") (pin "2") (pinfunction "2_2") (pintype "passive"))
      (node (ref "R56") (pin "2") (pinfunction "2_2") (pintype "passive"))
    )
    (net (code "60") (name "Net-(IC8B-IN)") (class "Default")
      (node (ref "IC8") (pin "7") (pinfunction "IN_7") (pintype "input"))
      (node (ref "R61") (pin "2") (pinfunction "2_2") (pintype "passive"))
      (node (ref "R66") (pin "2") (pinfunction "2_2") (pintype "passive"))
    )
    (net (code "61") (name "Net-(IC8C-IN)") (class "Default")
      (node (ref "IC8") (pin "10") (pinfunction "IN_10") (pintype "input"))
      (node (ref "R64") (pin "2") (pinfunction "2_2") (pintype "passive"))
      (node (ref "R67") (pin "2") (pinfunction "2_2") (pintype "passive"))
    )
    (net (code "62") (name "Net-(IC8D-IN)") (class "Default")
      (node (ref "IC8") (pin "15") (pinfunction "IN_15") (pintype "input"))
      (node (ref "R53") (pin "2") (pinfunction "2_2") (pintype "passive"))
      (node (ref "R57") (pin "2") (pinfunction "2_2") (pintype "passive"))
    )
    (net (code "63") (name "Net-(IC9A--IN)") (class "Default")
      (node (ref "IC9") (pin "2") (pinfunction "-IN_2") (pintype "input"))
      (node (ref "R71") (pin "1") (pinfunction "1_1") (pintype "passive"))
      (node (ref "R72") (pin "2") (pinfunction "2_2") (pintype "passive"))
      (node (ref "R73") (pin "1") (pinfunction "1_1") (pintype "passive"))
      (node (ref "R75") (pin "1") (pinfunction "1_1") (pintype "passive"))
    )
    (net (code "64") (name "Net-(IC9C-OUT)") (class "Default")
      (node (ref "C41") (pin "2") (pinfunction "2_2") (pintype "passive"))
      (node (ref "IC9") (pin "8") (pinfunction "OUT_8") (pintype "output"))
      (node (ref "JP13") (pin "2") (pinfunction "2_2") (pintype "passive"))
      (node (ref "R71") (pin "2") (pinfunction "2_2") (pintype "passive"))
    )
    (net (code "65") (name "Net-(IC9D-OUT)") (class "Default")
      (node (ref "IC9") (pin "14") (pinfunction "OUT_14") (pintype "output"))
      (node (ref "R73") (pin "2") (pinfunction "2_2") (pintype "passive"))
      (node (ref "R74") (pin "1") (pinfunction "1_1") (pintype "passive"))
      (node (ref "R88") (pin "1") (pinfunction "1_1") (pintype "passive"))
      (node (ref "R99") (pin "1") (pinfunction "1_1") (pintype "passive"))
    )
    (net (code "66") (name "Net-(IC10A--IN)") (class "Default")
      (node (ref "C38") (pin "2") (pinfunction "2_2") (pintype "passive"))
      (node (ref "IC10") (pin "2") (pinfunction "-IN_2") (pintype "input"))
      (node (ref "R69") (pin "P$3") (pinfunction "A_P$3") (pintype "passive"))
      (node (ref "R78") (pin "2") (pinfunction "2_2") (pintype "passive"))
      (node (ref "R79") (pin "2") (pinfunction "2_2") (pintype "passive"))
      (node (ref "R80") (pin "2") (pinfunction "2_2") (pintype "passive"))
      (node (ref "R84") (pin "1") (pinfunction "1_1") (pintype "passive"))
    )
    (net (code "67") (name "Net-(IC10A-OUT)") (class "Default")
      (node (ref "C38") (pin "1") (pinfunction "1_1") (pintype "passive"))
      (node (ref "D10") (pin "C") (pinfunction "C_C") (pintype "passive"))
      (node (ref "IC10") (pin "1") (pinfunction "OUT_1") (pintype "output"))
      (node (ref "IC11") (pin "11") (pinfunction "CTRL_11") (pintype "input"))
      (node (ref "R84") (pin "2") (pinfunction "2_2") (pintype "passive"))
    )
    (net (code "68") (name "Net-(IC10B--IN)") (class "Default")
      (node (ref "IC10") (pin "6") (pinfunction "-IN_6") (pintype "input"))
      (node (ref "R91") (pin "2") (pinfunction "2_2") (pintype "passive"))
      (node (ref "R92") (pin "1") (pinfunction "1_1") (pintype "passive"))
    )
    (net (code "69") (name "Net-(IC10B-OUT)") (class "Default")
      (node (ref "IC10") (pin "7") (pinfunction "OUT_7") (pintype "output"))
      (node (ref "R92") (pin "2") (pinfunction "2_2") (pintype "passive"))
      (node (ref "R95") (pin "1") (pinfunction "1_1") (pintype "passive"))
    )
    (net (code "70") (name "Net-(IC10C--IN)") (class "Default")
      (node (ref "C46") (pin "2") (pinfunction "2_2") (pintype "passive"))
      (node (ref "IC10") (pin "9") (pinfunction "-IN_9") (pintype "input"))
      (node (ref "R65") (pin "P$1") (pinfunction "E_P$1") (pintype "passive"))
      (node (ref "R93") (pin "1") (pinfunction "1_1") (pintype "passive"))
      (node (ref "R95") (pin "2") (pinfunction "2_2") (pintype "passive"))
      (node (ref "R96") (pin "2") (pinfunction "2_2") (pintype "passive"))
    )
    (net (code "71") (name "Net-(IC10C-OUT)") (class "Default")
      (node (ref "C46") (pin "1") (pinfunction "1_1") (pintype "passive"))
      (node (ref "D12") (pin "C") (pinfunction "C_C") (pintype "passive"))
      (node (ref "IC10") (pin "8") (pinfunction "OUT_8") (pintype "output"))
      (node (ref "IC11") (pin "6") (pinfunction "CTRL_6") (pintype "input"))
      (node (ref "R93") (pin "2") (pinfunction "2_2") (pintype "passive"))
    )
    (net (code "72") (name "Net-(IC10D--IN)") (class "Default")
      (node (ref "C39") (pin "2") (pinfunction "2_2") (pintype "passive"))
      (node (ref "D11") (pin "A") (pinfunction "A_A") (pintype "passive"))
      (node (ref "IC10") (pin "13") (pinfunction "-IN_13") (pintype "input"))
      (node (ref "R68") (pin "P$3") (pinfunction "A_P$3") (pintype "passive"))
      (node (ref "R81") (pin "2") (pinfunction "2_2") (pintype "passive"))
      (node (ref "R82") (pin "2") (pinfunction "2_2") (pintype "passive"))
      (node (ref "R85") (pin "1") (pinfunction "1_1") (pintype "passive"))
    )
    (net (code "73") (name "Net-(IC10D-OUT)") (class "Default")
      (node (ref "D11") (pin "C") (pinfunction "C_C") (pintype "passive"))
      (node (ref "D16") (pin "A") (pinfunction "A_A") (pintype "passive"))
      (node (ref "IC10") (pin "14") (pinfunction "OUT_14") (pintype "output"))
    )
    (net (code "74") (name "Net-(IC11A-CTRL)") (class "Default")
      (node (ref "C39") (pin "1") (pinfunction "1_1") (pintype "passive"))
      (node (ref "D16") (pin "C") (pinfunction "C_C") (pintype "passive"))
      (node (ref "IC11") (pin "14") (pinfunction "CTRL_14") (pintype "input"))
      (node (ref "IC11") (pin "3") (pinfunction "CTRL_3") (pintype "input"))
      (node (ref "R85") (pin "2") (pinfunction "2_2") (pintype "passive"))
    )
    (net (code "75") (name "Net-(IC11A-IN)") (class "Default")
      (node (ref "IC11") (pin "2") (pinfunction "IN_2") (pintype "input"))
      (node (ref "R86") (pin "2") (pinfunction "2_2") (pintype "passive"))
      (node (ref "R89") (pin "2") (pinfunction "2_2") (pintype "passive"))
    )
    (net (code "76") (name "Net-(IC11A-OUT)") (class "Default")
      (node (ref "C40") (pin "1") (pinfunction "1_1") (pintype "passive"))
      (node (ref "IC11") (pin "4") (pinfunction "OUT_4") (pintype "output"))
      (node (ref "IC9") (pin "6") (pinfunction "-IN_6") (pintype "input"))
    )
    (net (code "77") (name "Net-(IC11B-IN)") (class "Default")
      (node (ref "IC11") (pin "7") (pinfunction "IN_7") (pintype "input"))
      (node (ref "R94") (pin "2") (pinfunction "2_2") (pintype "passive"))
      (node (ref "R98") (pin "2") (pinfunction "2_2") (pintype "passive"))
    )
    (net (code "78") (name "Net-(IC11B-OUT)") (class "Default")
      (node (ref "IC11") (pin "5") (pinfunction "OUT_5") (pintype "output"))
      (node (ref "IC9") (pin "13") (pinfunction "-IN_13") (pintype "input"))
      (node (ref "R76") (pin "2") (pinfunction "2_2") (pintype "passive"))
    )
    (net (code "79") (name "Net-(IC11C-IN)") (class "Default")
      (node (ref "IC11") (pin "10") (pinfunction "IN_10") (pintype "input"))
      (node (ref "R97") (pin "2") (pinfunction "2_2") (pintype "passive"))
      (node (ref "R99") (pin "2") (pinfunction "2_2") (pintype "passive"))
    )
    (net (code "80") (name "Net-(IC11D-IN)") (class "Default")
      (node (ref "IC11") (pin "15") (pinfunction "IN_15") (pintype "input"))
      (node (ref "R87") (pin "2") (pinfunction "2_2") (pintype "passive"))
      (node (ref "R90") (pin "2") (pinfunction "2_2") (pintype "passive"))
    )
    (net (code "81") (name "Net-(IC11D-OUT)") (class "Default")
      (node (ref "C41") (pin "1") (pinfunction "1_1") (pintype "passive"))
      (node (ref "IC11") (pin "13") (pinfunction "OUT_13") (pintype "output"))
      (node (ref "IC9") (pin "9") (pinfunction "-IN_9") (pintype "input"))
    )
    (net (code "82") (name "Net-(IC12A--IN)") (class "Default")
      (node (ref "IC12") (pin "2") (pinfunction "-IN_2") (pintype "input"))
      (node (ref "R102") (pin "1") (pinfunction "1_1") (pintype "passive"))
      (node (ref "R105") (pin "2") (pinfunction "2_2") (pintype "passive"))
    )
    (net (code "83") (name "Net-(IC12A-OUT)") (class "Default")
      (node (ref "IC12") (pin "1") (pinfunction "OUT_1") (pintype "output"))
      (node (ref "R102") (pin "2") (pinfunction "2_2") (pintype "passive"))
      (node (ref "R106") (pin "1") (pinfunction "1_1") (pintype "passive"))
    )
    (net (code "84") (name "Net-(IC12B--IN)") (class "Default")
      (node (ref "IC12") (pin "6") (pinfunction "-IN_6") (pintype "input"))
      (node (ref "R103") (pin "1") (pinfunction "1_1") (pintype "passive"))
      (node (ref "R106") (pin "2") (pinfunction "2_2") (pintype "passive"))
      (node (ref "R122") (pin "1") (pinfunction "1_1") (pintype "passive"))
    )
    (net (code "85") (name "Net-(IC13B-OUT)") (class "Default")
      (node (ref "IC13") (pin "7") (pinfunction "OUT_7") (pintype "output"))
      (node (ref "R104") (pin "1") (pinfunction "1_1") (pintype "passive"))
      (node (ref "R110") (pin "2") (pinfunction "2_2") (pintype "passive"))
    )
    (net (code "86") (name "Net-(IC14A-+IN)") (class "Default")
      (node (ref "IC14") (pin "3") (pinfunction "+IN_3") (pintype "input"))
      (node (ref "IC14") (pin "6") (pinfunction "-IN_6") (pintype "input"))
      (node (ref "R115") (pin "2") (pinfunction "2_2") (pintype "passive"))
      (node (ref "R117") (pin "2") (pinfunction "2_2") (pintype "passive"))
      (node (ref "R118") (pin "1") (pinfunction "1_1") (pintype "passive"))
    )
    (net (code "87") (name "Net-(IC14A--IN)") (class "Default")
      (node (ref "IC14") (pin "2") (pinfunction "-IN_2") (pintype "input"))
      (node (ref "R119") (pin "2") (pinfunction "2_2") (pintype "passive"))
      (node (ref "R121") (pin "1") (pinfunction "1_1") (pintype "passive"))
    )
    (net (code "88") (name "Net-(IC14A-OUT)") (class "Default")
      (node (ref "D13") (pin "A") (pinfunction "A_A") (pintype "passive"))
      (node (ref "IC14") (pin "1") (pinfunction "OUT_1") (pintype "output"))
    )
    (net (code "89") (name "Net-(IC14B-+IN)") (class "Default")
      (node (ref "IC14") (pin "5") (pinfunction "+IN_5") (pintype "input"))
      (node (ref "R119") (pin "1") (pinfunction "1_1") (pintype "passive"))
      (node (ref "R120") (pin "2") (pinfunction "2_2") (pintype "passive"))
    )
    (net (code "90") (name "Net-(IC14B-OUT)") (class "Default")
      (node (ref "D14") (pin "A") (pinfunction "A_A") (pintype "passive"))
      (node (ref "IC14") (pin "7") (pinfunction "OUT_7") (pintype "output"))
    )
    (net (code "91") (name "Net-(J1-3)") (class "Default")
      (node (ref "J1") (pin "P3") (pinfunction "3_P3") (pintype "passive"))
      (node (ref "R6") (pin "1") (pinfunction "1_1") (pintype "passive"))
    )
    (net (code "92") (name "Net-(J2-3)") (class "Default")
      (node (ref "J2") (pin "P3") (pinfunction "3_P3") (pintype "passive"))
      (node (ref "R30") (pin "1") (pinfunction "1_1") (pintype "passive"))
    )
    (net (code "93") (name "Net-(J3-3)") (class "Default")
      (node (ref "J3") (pin "P3") (pinfunction "3_P3") (pintype "passive"))
      (node (ref "R48") (pin "1") (pinfunction "1_1") (pintype "passive"))
    )
    (net (code "94") (name "Net-(J4-3)") (class "Default")
      (node (ref "J4") (pin "P3") (pinfunction "3_P3") (pintype "passive"))
      (node (ref "R45") (pin "1") (pinfunction "1_1") (pintype "passive"))
    )
    (net (code "95") (name "Net-(J5-3)") (class "Default")
      (node (ref "J5") (pin "P3") (pinfunction "3_P3") (pintype "passive"))
      (node (ref "R58") (pin "1") (pinfunction "1_1") (pintype "passive"))
    )
    (net (code "96") (name "Net-(J6-3)") (class "Default")
      (node (ref "J6") (pin "P3") (pinfunction "3_P3") (pintype "passive"))
      (node (ref "R91") (pin "1") (pinfunction "1_1") (pintype "passive"))
    )
    (net (code "97") (name "Net-(J7-3)") (class "Default")
      (node (ref "J7") (pin "P3") (pinfunction "3_P3") (pintype "passive"))
      (node (ref "R82") (pin "1") (pinfunction "1_1") (pintype "passive"))
    )
    (net (code "98") (name "Net-(J8-3)") (class "Default")
      (node (ref "J8") (pin "P3") (pinfunction "3_P3") (pintype "passive"))
      (node (ref "R78") (pin "1") (pinfunction "1_1") (pintype "passive"))
    )
    (net (code "99") (name "Net-(J9-3)") (class "Default")
      (node (ref "J9") (pin "P3") (pinfunction "3_P3") (pintype "passive"))
      (node (ref "R9") (pin "1") (pinfunction "1_1") (pintype "passive"))
    )
    (net (code "100") (name "Net-(J10-3)") (class "Default")
      (node (ref "J10") (pin "P3") (pinfunction "3_P3") (pintype "passive"))
      (node (ref "R27") (pin "1") (pinfunction "1_1") (pintype "passive"))
    )
    (net (code "101") (name "Net-(J13-3)") (class "Default")
      (node (ref "J13") (pin "P3") (pinfunction "3_P3") (pintype "passive"))
      (node (ref "R105") (pin "1") (pinfunction "1_1") (pintype "passive"))
    )
    (net (code "102") (name "Net-(J14-3)") (class "Default")
      (node (ref "J14") (pin "P3") (pinfunction "3_P3") (pintype "passive"))
      (node (ref "R111") (pin "2") (pinfunction "2_2") (pintype "passive"))
    )
    (net (code "103") (name "Net-(JP11-Pad10)") (class "Default")
      (node (ref "JP11") (pin "10") (pinfunction "10_10") (pintype "passive"))
      (node (ref "JP11") (pin "9") (pinfunction "9_9") (pintype "passive"))
      (node (ref "P1") (pin "2") (pinfunction "2_2") (pintype "bidirectional"))
    )
    (net (code "104") (name "Net-(JP12-Pad2)") (class "Default")
      (node (ref "JP12") (pin "2") (pinfunction "2_2") (pintype "passive"))
      (node (ref "R122") (pin "2") (pinfunction "2_2") (pintype "passive"))
    )
    (net (code "105") (name "Net-(LED1-C)") (class "Default")
      (node (ref "LED1") (pin "K") (pinfunction "C_K") (pintype "passive"))
      (node (ref "Q1") (pin "C") (pinfunction "C_C") (pintype "passive"))
    )
    (net (code "106") (name "Net-(LED1-PadA)") (class "Default")
      (node (ref "LED1") (pin "A") (pinfunction "A_A") (pintype "passive"))
      (node (ref "R112") (pin "1") (pinfunction "1_1") (pintype "passive"))
    )
    (net (code "107") (name "Net-(Q1-PadB)") (class "Default")
      (node (ref "Q1") (pin "B") (pinfunction "B_B") (pintype "passive"))
      (node (ref "R114") (pin "2") (pinfunction "2_2") (pintype "passive"))
      (node (ref "R116") (pin "2") (pinfunction "2_2") (pintype "passive"))
    )
    (net (code "108") (name "Net-(R3-S)") (class "Default")
      (node (ref "R3") (pin "P$2") (pinfunction "S_P$2") (pintype "passive"))
      (node (ref "R5") (pin "2") (pinfunction "2_2") (pintype "passive"))
    )
    (net (code "109") (name "Net-(R4-S)") (class "Default")
      (node (ref "R12") (pin "2") (pinfunction "2_2") (pintype "passive"))
      (node (ref "R4") (pin "P$2") (pinfunction "S_P$2") (pintype "passive"))
    )
    (net (code "110") (name "Net-(R34-S)") (class "Default")
      (node (ref "R34") (pin "P$2") (pinfunction "S_P$2") (pintype "passive"))
      (node (ref "R43") (pin "2") (pinfunction "2_2") (pintype "passive"))
    )
    (net (code "111") (name "Net-(R36-S)") (class "Default")
      (node (ref "R36") (pin "P$2") (pinfunction "S_P$2") (pintype "passive"))
      (node (ref "R49") (pin "2") (pinfunction "2_2") (pintype "passive"))
    )
    (net (code "112") (name "Net-(R39-Pad2)") (class "Default")
      (node (ref "R39") (pin "2") (pinfunction "2_2") (pintype "passive"))
      (node (ref "R41") (pin "1") (pinfunction "1_1") (pintype "passive"))
    )
    (net (code "113") (name "Net-(R42-S)") (class "Default")
      (node (ref "R42") (pin "P$2") (pinfunction "S_P$2") (pintype "passive"))
      (node (ref "R54") (pin "2") (pinfunction "2_2") (pintype "passive"))
    )
    (net (code "114") (name "Net-(R65-S)") (class "Default")
      (node (ref "R65") (pin "P$2") (pinfunction "S_P$2") (pintype "passive"))
      (node (ref "R70") (pin "2") (pinfunction "2_2") (pintype "passive"))
    )
    (net (code "115") (name "Net-(R68-S)") (class "Default")
      (node (ref "R68") (pin "P$2") (pinfunction "S_P$2") (pintype "passive"))
      (node (ref "R77") (pin "2") (pinfunction "2_2") (pintype "passive"))
    )
    (net (code "116") (name "Net-(R69-S)") (class "Default")
      (node (ref "R69") (pin "P$2") (pinfunction "S_P$2") (pintype "passive"))
      (node (ref "R83") (pin "2") (pinfunction "2_2") (pintype "passive"))
    )
    (net (code "117") (name "Net-(R74-Pad2)") (class "Default")
      (node (ref "R74") (pin "2") (pinfunction "2_2") (pintype "passive"))
      (node (ref "R76") (pin "1") (pinfunction "1_1") (pintype "passive"))
    )
    (net (code "118") (name "Net-(R100-S)") (class "Default")
      (node (ref "R100") (pin "P$2") (pinfunction "S_P$2") (pintype "passive"))
      (node (ref "R109") (pin "2") (pinfunction "2_2") (pintype "passive"))
    )
    (net (code "119") (name "Net-(R101-S)") (class "Default")
      (node (ref "R101") (pin "P$2") (pinfunction "S_P$2") (pintype "passive"))
      (node (ref "R108") (pin "2") (pinfunction "2_2") (pintype "passive"))
    )
    (net (code "120") (name "OUTPUT") (class "Default")
      (node (ref "C57") (pin "2") (pinfunction "2_2") (pintype "passive"))
      (node (ref "IC13") (pin "1") (pinfunction "OUT_1") (pintype "output"))
      (node (ref "R107") (pin "2") (pinfunction "2_2") (pintype "passive"))
      (node (ref "R111") (pin "1") (pinfunction "1_1") (pintype "passive"))
    )
    (net (code "121") (name "PLUS_BUS") (class "Default")
      (node (ref "IC13") (pin "6") (pinfunction "-IN_6") (pintype "input"))
      (node (ref "IC5") (pin "12") (pinfunction "OUT_12") (pintype "output"))
      (node (ref "R110") (pin "1") (pinfunction "1_1") (pintype "passive"))
      (node (ref "R33") (pin "2") (pinfunction "2_2") (pintype "passive"))
      (node (ref "R55") (pin "2") (pinfunction "2_2") (pintype "passive"))
      (node (ref "R88") (pin "2") (pinfunction "2_2") (pintype "passive"))
    )
    (net (code "122") (name "VCC") (class "Default")
      (node (ref "C1") (pin "+") (pinfunction "+_+") (pintype "passive"))
      (node (ref "C12") (pin "1") (pinfunction "1_1") (pintype "passive"))
      (node (ref "C21") (pin "1") (pinfunction "1_1") (pintype "passive"))
      (node (ref "C27") (pin "1") (pinfunction "1_1") (pintype "passive"))
      (node (ref "C31") (pin "1") (pinfunction "1_1") (pintype "passive"))
      (node (ref "C36") (pin "1") (pinfunction "1_1") (pintype "passive"))
      (node (ref "C42") (pin "1") (pinfunction "1_1") (pintype "passive"))
      (node (ref "C43") (pin "1") (pinfunction "1_1") (pintype "passive"))
      (node (ref "C5") (pin "1") (pinfunction "1_1") (pintype "passive"))
      (node (ref "C50") (pin "1") (pinfunction "1_1") (pintype "passive"))
      (node (ref "C52") (pin "1") (pinfunction "1_1") (pintype "passive"))
      (node (ref "C56") (pin "1") (pinfunction "1_1") (pintype "passive"))
      (node (ref "C58") (pin "+") (pinfunction "+_+") (pintype "passive"))
      (node (ref "C9") (pin "1") (pinfunction "1_1") (pintype "passive"))
      (node (ref "D2") (pin "C") (pinfunction "C_C") (pintype "passive"))
      (node (ref "IC10") (pin "4") (pinfunction "V+_4") (pintype "power_in"))
      (node (ref "IC11") (pin "16") (pinfunction "V+_16") (pintype "power_in"))
      (node (ref "IC12") (pin "8") (pinfunction "V+_8") (pintype "power_in"))
      (node (ref "IC13") (pin "8") (pinfunction "V+_8") (pintype "power_in"))
      (node (ref "IC14") (pin "8") (pinfunction "V+_8") (pintype "power_in"))
      (node (ref "IC3") (pin "8") (pinfunction "V+_8") (pintype "power_in"))
      (node (ref "IC4") (pin "4") (pinfunction "V+_4") (pintype "power_in"))
      (node (ref "IC5") (pin "16") (pinfunction "V+_16") (pintype "power_in"))
      (node (ref "IC6") (pin "4") (pinfunction "V+_4") (pintype "power_in"))
      (node (ref "IC7") (pin "4") (pinfunction "V+_4") (pintype "power_in"))
      (node (ref "IC8") (pin "16") (pinfunction "V+_16") (pintype "power_in"))
      (node (ref "IC9") (pin "4") (pinfunction "V+_4") (pintype "power_in"))
      (node (ref "R1") (pin "1") (pinfunction "1_1") (pintype "passive"))
      (node (ref "R112") (pin "2") (pinfunction "2_2") (pintype "passive"))
    )
    (net (code "123") (name "VEE") (class "Default")
      (node (ref "C13") (pin "2") (pinfunction "2_2") (pintype "passive"))
      (node (ref "C2") (pin "-") (pinfunction "-_-") (pintype "passive"))
      (node (ref "C20") (pin "2") (pinfunction "2_2") (pintype "passive"))
      (node (ref "C22") (pin "2") (pinfunction "2_2") (pintype "passive"))
      (node (ref "C28") (pin "2") (pinfunction "2_2") (pintype "passive"))
      (node (ref "C35") (pin "2") (pinfunction "2_2") (pintype "passive"))
      (node (ref "C37") (pin "2") (pinfunction "2_2") (pintype "passive"))
      (node (ref "C44") (pin "2") (pinfunction "2_2") (pintype "passive"))
      (node (ref "C51") (pin "2") (pinfunction "2_2") (pintype "passive"))
      (node (ref "C53") (pin "2") (pinfunction "2_2") (pintype "passive"))
      (node (ref "C54") (pin "2") (pinfunction "2_2") (pintype "passive"))
      (node (ref "C8") (pin "2") (pinfunction "2_2") (pintype "passive"))
      (node (ref "D1") (pin "A") (pinfunction "A_A") (pintype "passive"))
      (node (ref "IC10") (pin "11") (pinfunction "V-_11") (pintype "power_in"))
      (node (ref "IC11") (pin "9") (pinfunction "V-_9") (pintype "power_in"))
      (node (ref "IC12") (pin "4") (pinfunction "V-_4") (pintype "power_in"))
      (node (ref "IC13") (pin "4") (pinfunction "V-_4") (pintype "power_in"))
      (node (ref "IC3") (pin "4") (pinfunction "V-_4") (pintype "power_in"))
      (node (ref "IC4") (pin "11") (pinfunction "V-_11") (pintype "power_in"))
      (node (ref "IC5") (pin "9") (pinfunction "V-_9") (pintype "power_in"))
      (node (ref "IC6") (pin "11") (pinfunction "V-_11") (pintype "power_in"))
      (node (ref "IC7") (pin "11") (pinfunction "V-_11") (pintype "power_in"))
      (node (ref "IC8") (pin "9") (pinfunction "V-_9") (pintype "power_in"))
      (node (ref "IC9") (pin "11") (pinfunction "V-_11") (pintype "power_in"))
      (node (ref "P1") (pin "1") (pinfunction "1_1") (pintype "bidirectional"))
      (node (ref "R2") (pin "1") (pinfunction "1_1") (pintype "passive"))
    )
    (net (code "124") (name "unconnected-(IC5E-MODE-Pad1)") (class "Default")
      (node (ref "IC5") (pin "1") (pinfunction "MODE_1") (pintype "input"))
    )
    (net (code "125") (name "unconnected-(IC8E-MODE-Pad1)") (class "Default")
      (node (ref "IC8") (pin "1") (pinfunction "MODE_1") (pintype "input"))
    )
    (net (code "126") (name "unconnected-(IC11E-MODE-Pad1)") (class "Default")
      (node (ref "IC11") (pin "1") (pinfunction "MODE_1") (pintype "input"))
    )
    (net (code "127") (name "unconnected-(J1-2-PadP2)") (class "Default")
      (node (ref "J1") (pin "P2") (pinfunction "2_P2") (pintype "passive"))
    )
    (net (code "128") (name "unconnected-(J2-2-PadP2)") (class "Default")
      (node (ref "J2") (pin "P2") (pinfunction "2_P2") (pintype "passive"))
    )
    (net (code "129") (name "unconnected-(J3-2-PadP2)") (class "Default")
      (node (ref "J3") (pin "P2") (pinfunction "2_P2") (pintype "passive"))
    )
    (net (code "130") (name "unconnected-(J4-2-PadP2)") (class "Default")
      (node (ref "J4") (pin "P2") (pinfunction "2_P2") (pintype "passive"))
    )
    (net (code "131") (name "unconnected-(J5-2-PadP2)") (class "Default")
      (node (ref "J5") (pin "P2") (pinfunction "2_P2") (pintype "passive"))
    )
    (net (code "132") (name "unconnected-(J6-2-PadP2)") (class "Default")
      (node (ref "J6") (pin "P2") (pinfunction "2_P2") (pintype "passive"))
    )
    (net (code "133") (name "unconnected-(J7-2-PadP2)") (class "Default")
      (node (ref "J7") (pin "P2") (pinfunction "2_P2") (pintype "passive"))
    )
    (net (code "134") (name "unconnected-(J8-2-PadP2)") (class "Default")
      (node (ref "J8") (pin "P2") (pinfunction "2_P2") (pintype "passive"))
    )
    (net (code "135") (name "unconnected-(J9-2-PadP2)") (class "Default")
      (node (ref "J9") (pin "P2") (pinfunction "2_P2") (pintype "passive"))
    )
    (net (code "136") (name "unconnected-(J10-2-PadP2)") (class "Default")
      (node (ref "J10") (pin "P2") (pinfunction "2_P2") (pintype "passive"))
    )
    (net (code "137") (name "unconnected-(J11-2-PadP2)") (class "Default")
      (node (ref "J11") (pin "P2") (pinfunction "2_P2") (pintype "passive"))
    )
    (net (code "138") (name "unconnected-(J12-2-PadP2)") (class "Default")
      (node (ref "J12") (pin "P2") (pinfunction "2_P2") (pintype "passive"))
    )
    (net (code "139") (name "unconnected-(J13-2-PadP2)") (class "Default")
      (node (ref "J13") (pin "P2") (pinfunction "2_P2") (pintype "passive"))
    )
    (net (code "140") (name "unconnected-(J14-2-PadP2)") (class "Default")
      (node (ref "J14") (pin "P2") (pinfunction "2_P2") (pintype "passive"))
    )
    (net (code "141") (name "unconnected-(JP12-Pad1)") (class "Default")
      (node (ref "JP12") (pin "1") (pinfunction "1_1") (pintype "passive"))
    )
  )
)
